# GMSL_DESERIALIZER.net
KiCad netlist of a schematic drawn in Altium Designer
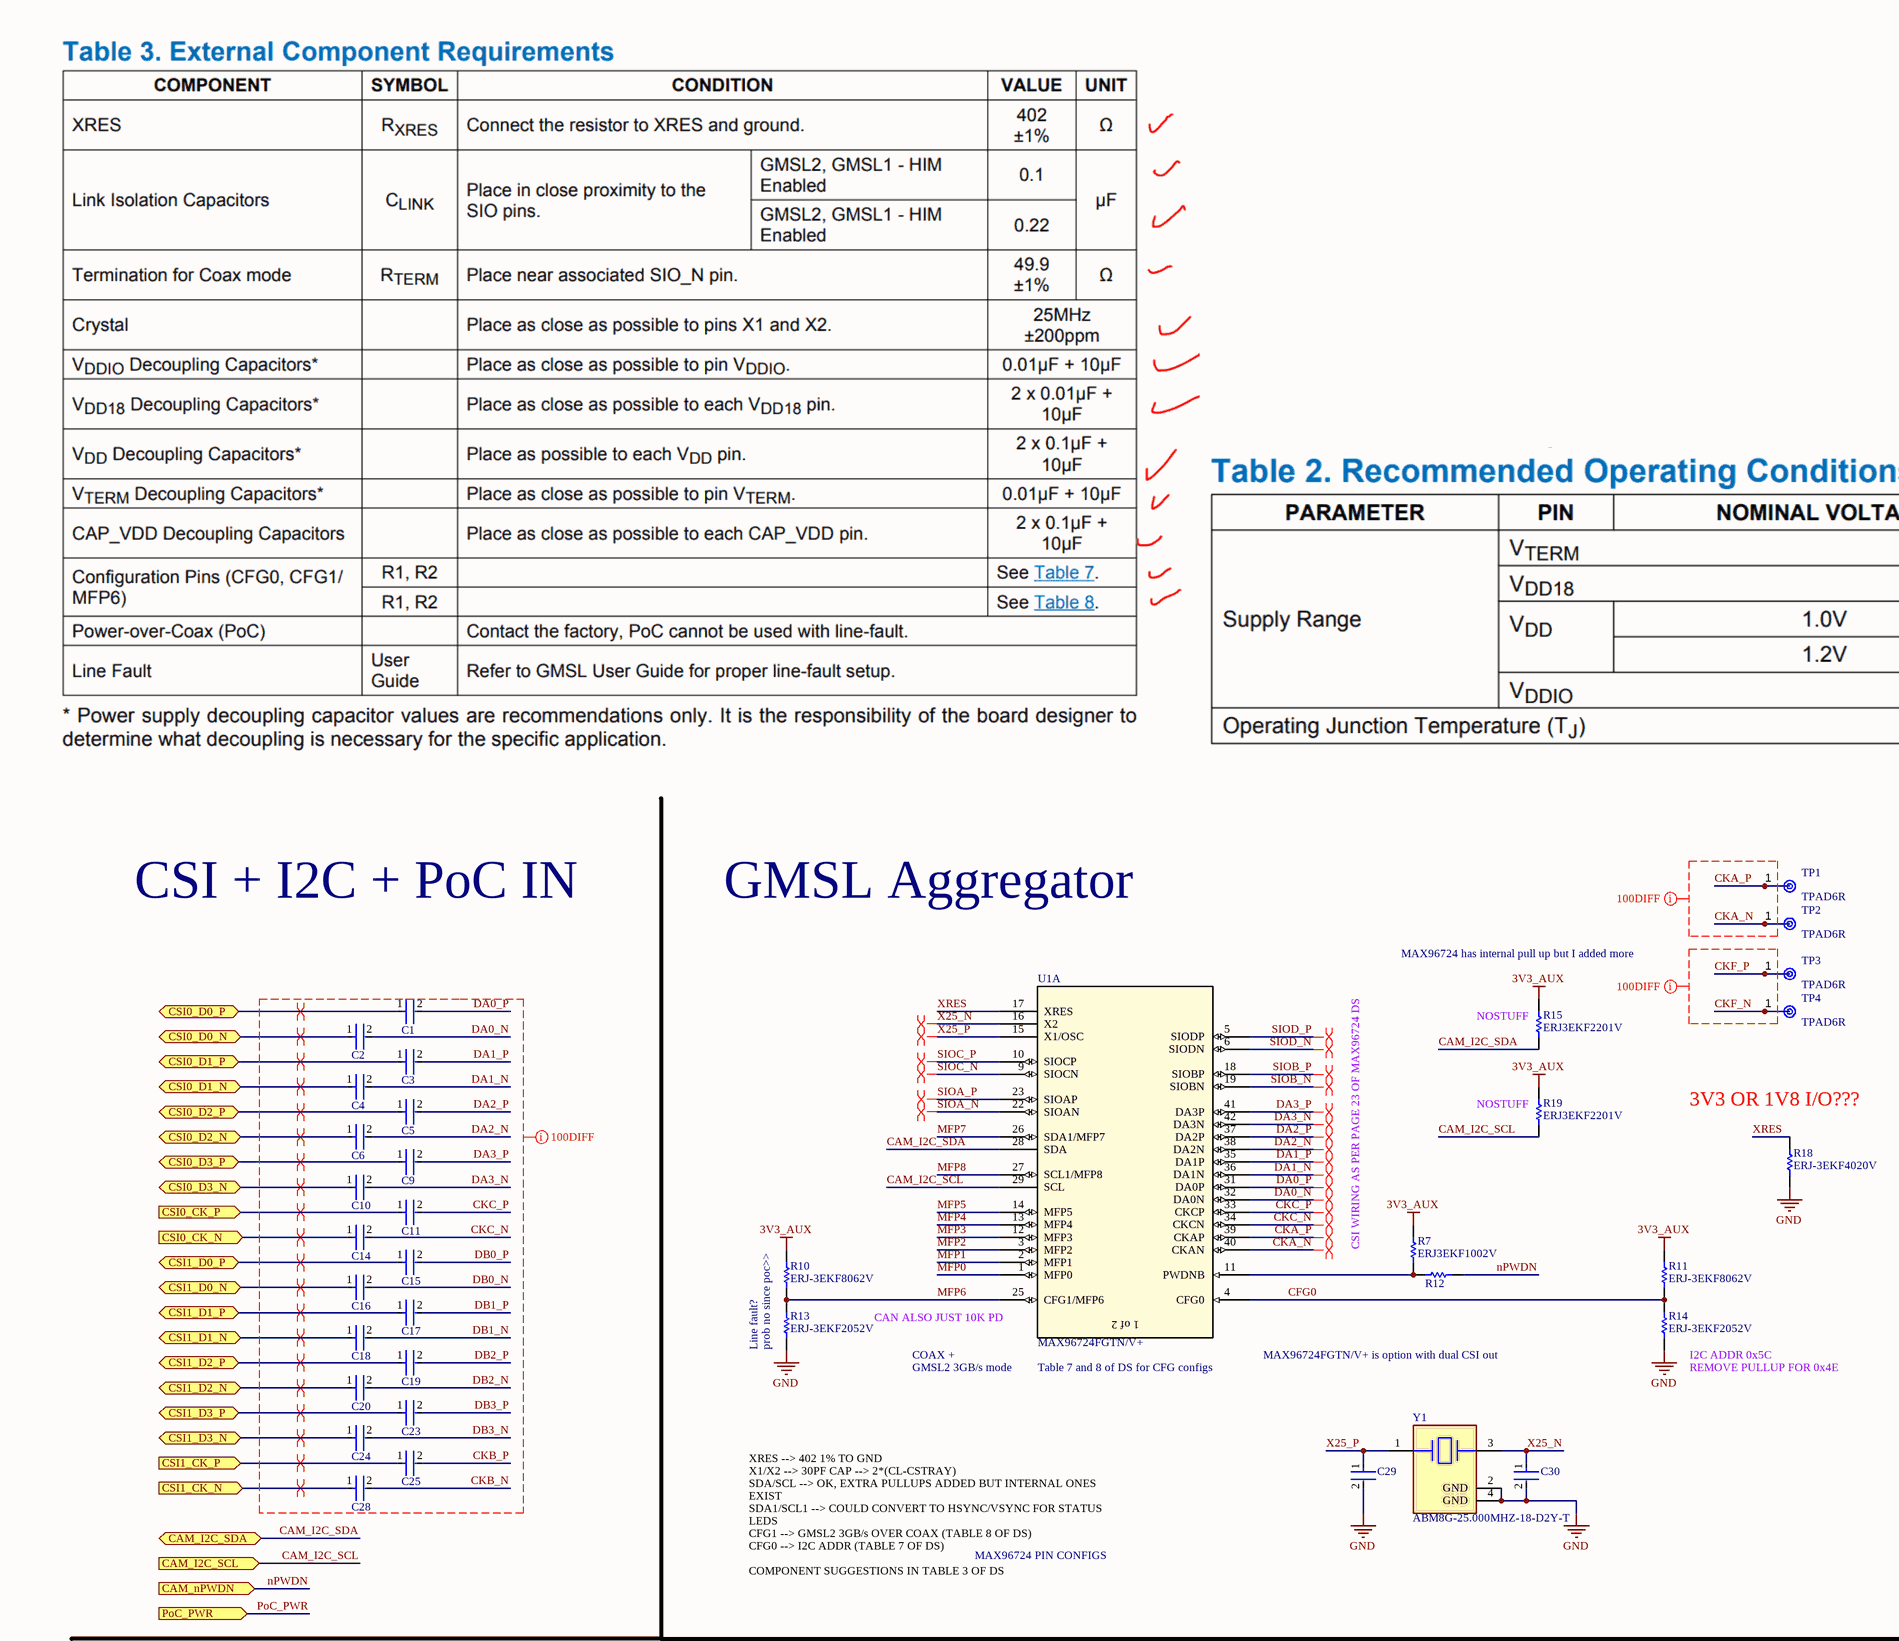
[diagram p0: GMSL_DESERIALIZER.SchDoc, top left]
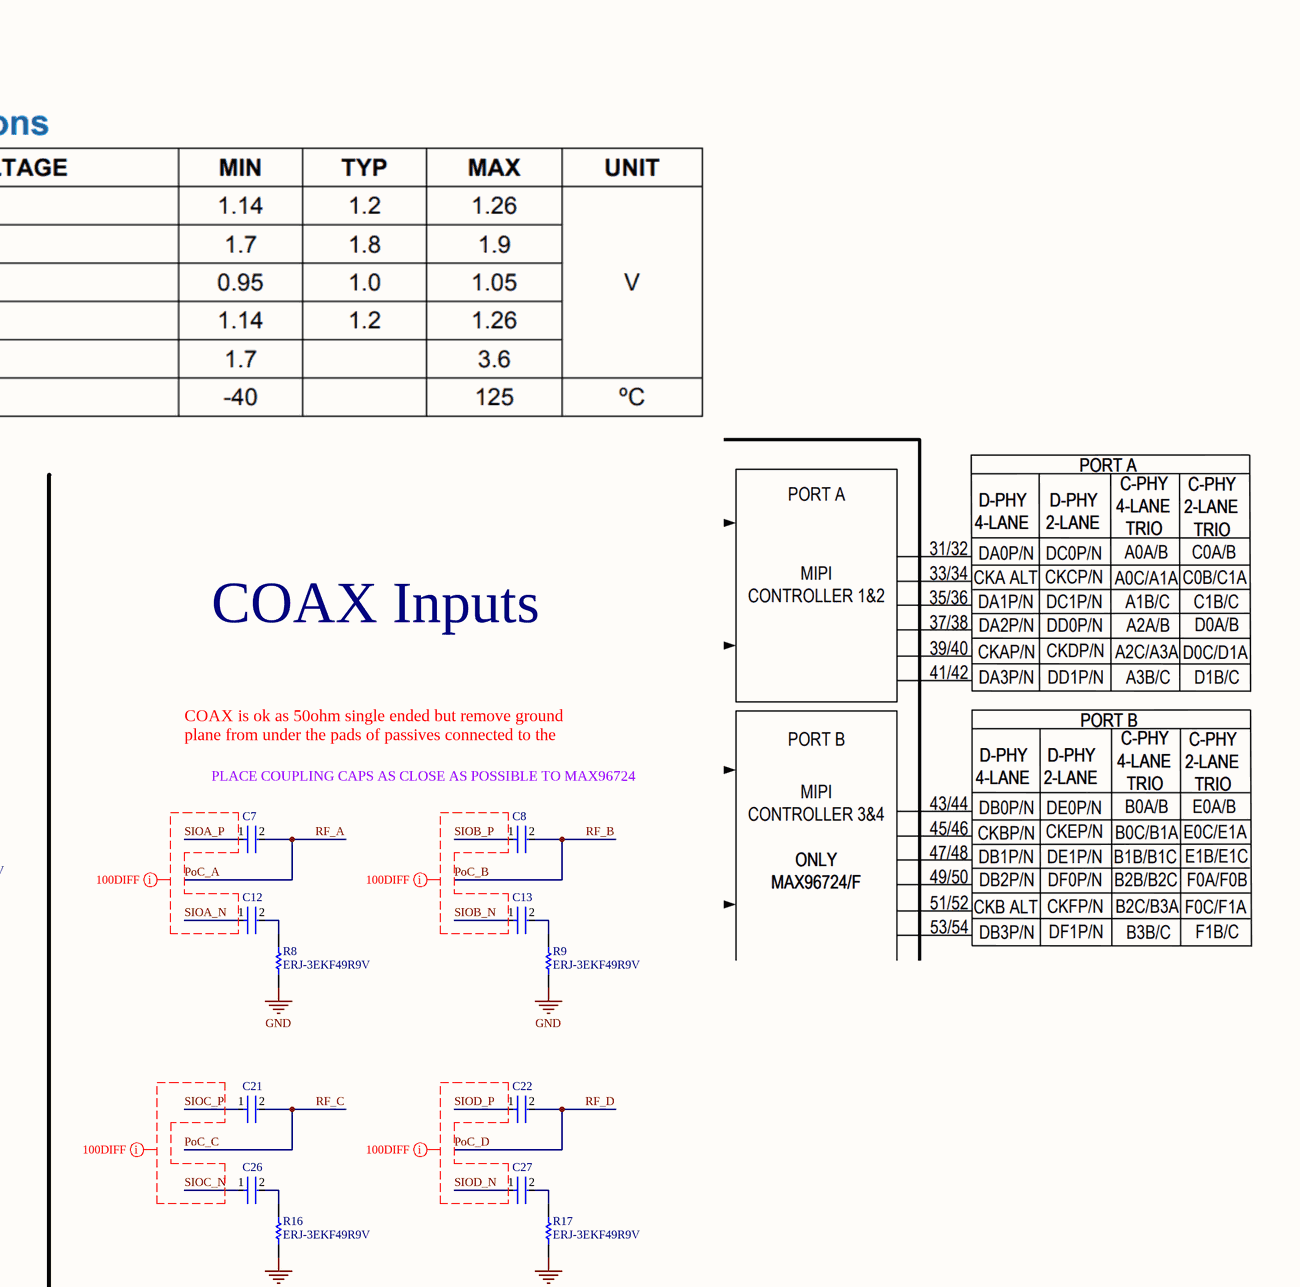
[diagram p1: GMSL_DESERIALIZER.SchDoc, top right]
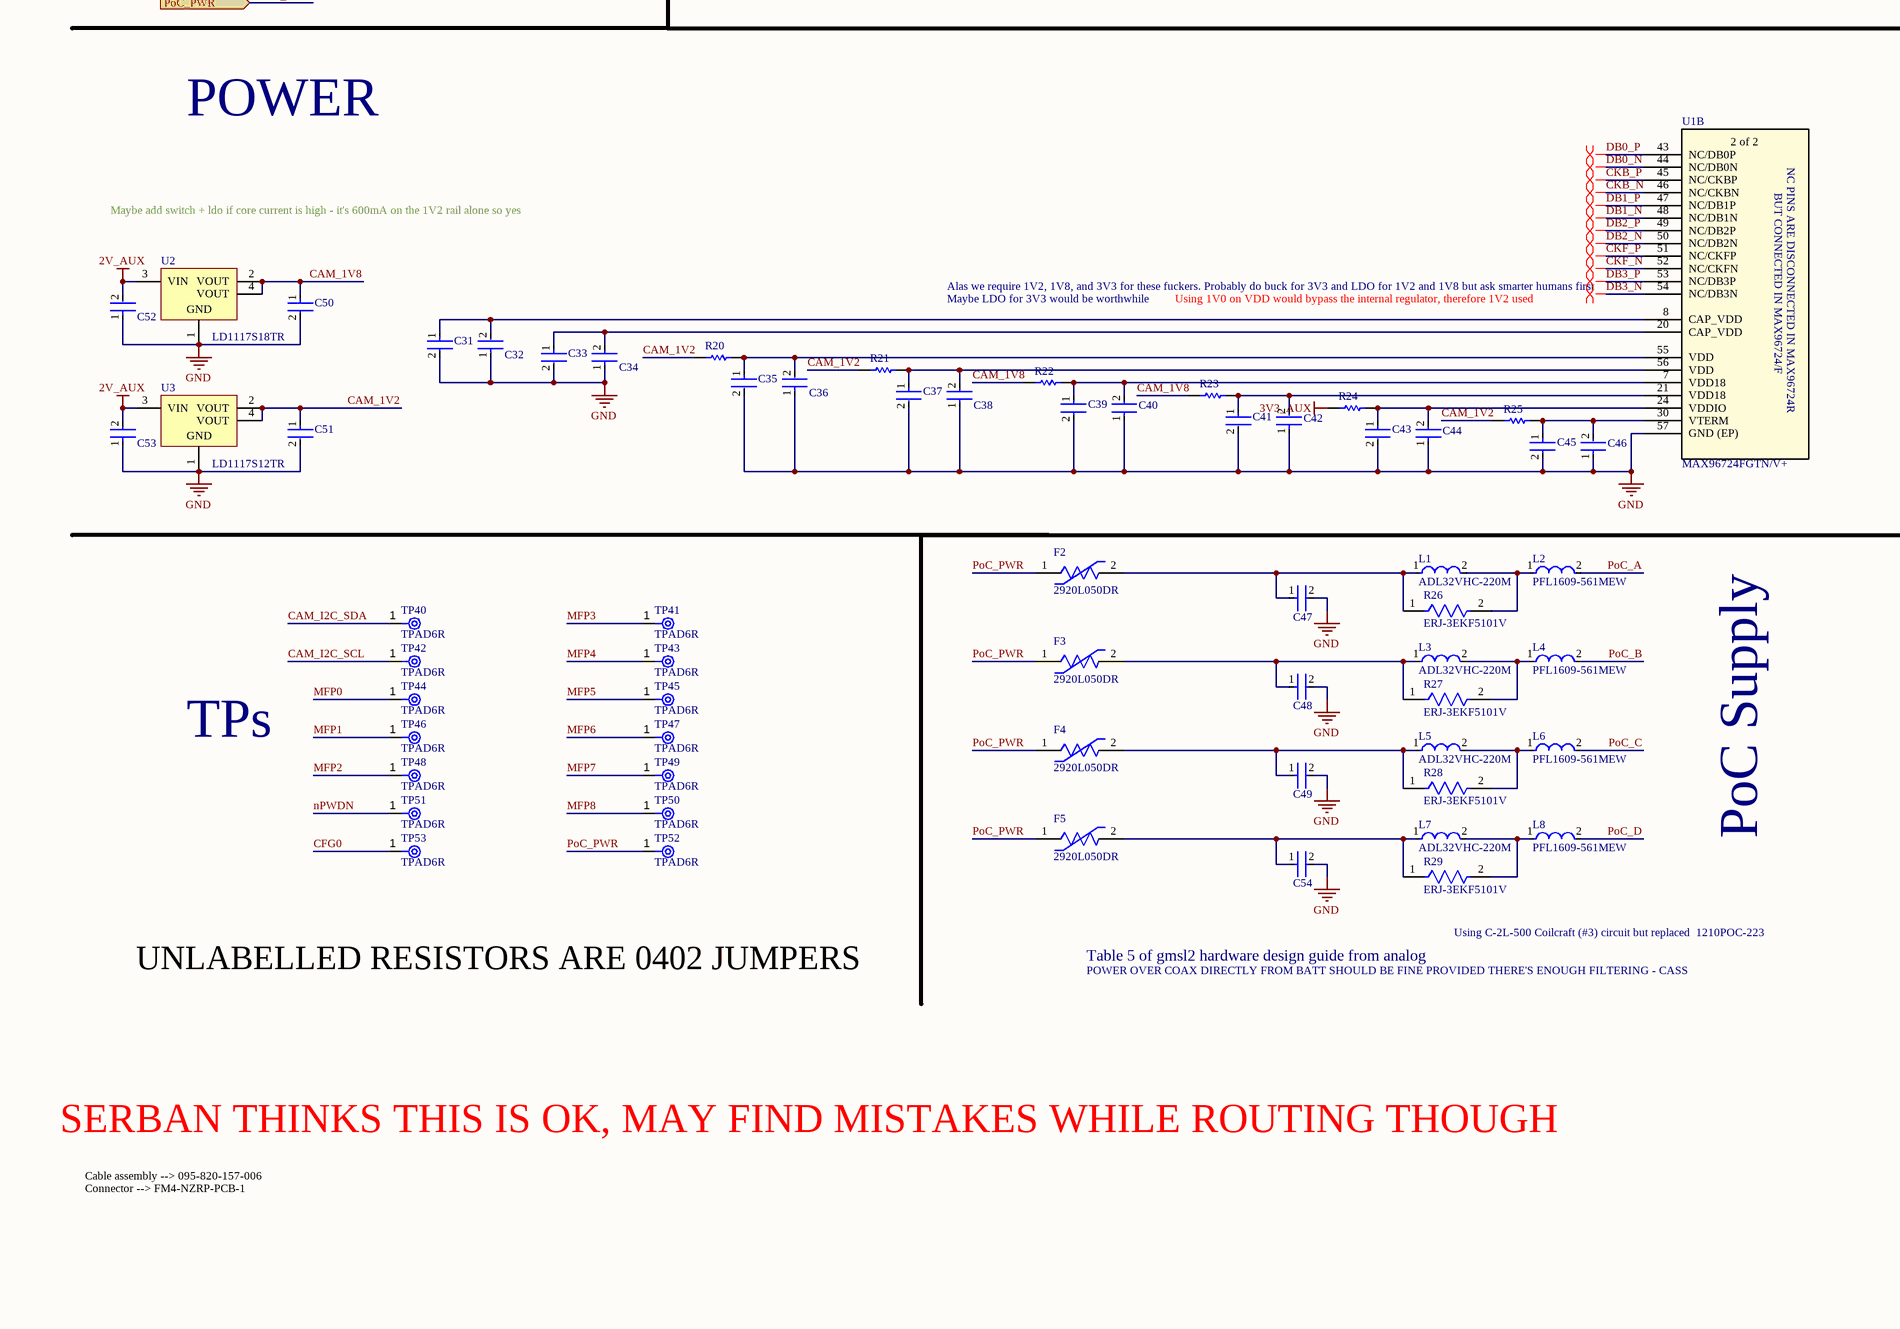
[diagram p2: GMSL_DESERIALIZER.SchDoc, bottom left]
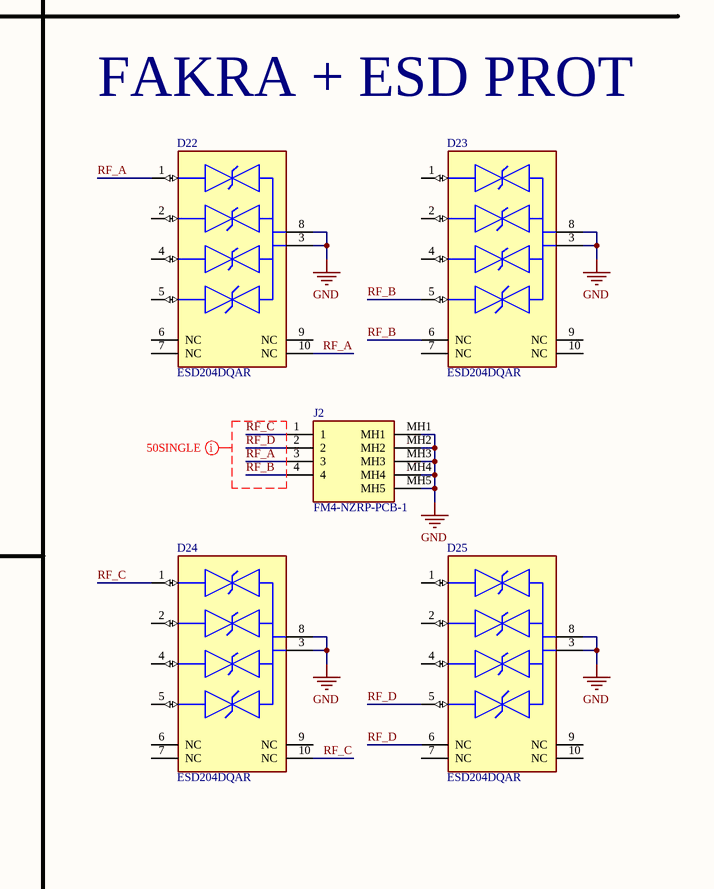
[diagram p3: GMSL_DESERIALIZER.SchDoc, bottom right]

(export (version "E")
  (design (tool "Eeschema 10.0.6"))
  (components
    (comp (ref "C1")
      (value "C1005X7R1H104K050BB")
      (footprint "FP-C1005-050-0_05-IPC_C")
      (description "Multilayer Ceramic Capacitors 100nF ±10% 50V X7R SMD 0402")
      (fields (field (name "VOLTAGE") "50V") (field (name "TOLERANCE") "10%"))
      (libsource (lib "Altium Content Vault") (part "b4654b650e69147ec39a6b967a45e02"))
    )
    (comp (ref "C2")
      (value "C1005X7R1H104K050BB")
      (footprint "FP-C1005-050-0_05-IPC_C")
      (description "Multilayer Ceramic Capacitors 100nF ±10% 50V X7R SMD 0402")
      (fields (field (name "VOLTAGE") "50V") (field (name "TOLERANCE") "10%"))
      (libsource (lib "Altium Content Vault") (part "b4654b650e69147ec39a6b967a45e02"))
    )
    (comp (ref "C3")
      (value "C1005X7R1H104K050BB")
      (footprint "FP-C1005-050-0_05-IPC_C")
      (description "Multilayer Ceramic Capacitors 100nF ±10% 50V X7R SMD 0402")
      (fields (field (name "VOLTAGE") "50V") (field (name "TOLERANCE") "10%"))
      (libsource (lib "Altium Content Vault") (part "b4654b650e69147ec39a6b967a45e02"))
    )
    (comp (ref "C4")
      (value "C1005X7R1H104K050BB")
      (footprint "FP-C1005-050-0_05-IPC_C")
      (description "Multilayer Ceramic Capacitors 100nF ±10% 50V X7R SMD 0402")
      (fields (field (name "VOLTAGE") "50V") (field (name "TOLERANCE") "10%"))
      (libsource (lib "Altium Content Vault") (part "b4654b650e69147ec39a6b967a45e02"))
    )
    (comp (ref "C5")
      (value "C1005X7R1H104K050BB")
      (footprint "FP-C1005-050-0_05-IPC_C")
      (description "Multilayer Ceramic Capacitors 100nF ±10% 50V X7R SMD 0402")
      (fields (field (name "VOLTAGE") "50V") (field (name "TOLERANCE") "10%"))
      (libsource (lib "Altium Content Vault") (part "b4654b650e69147ec39a6b967a45e02"))
    )
    (comp (ref "C6")
      (value "C1005X7R1H104K050BB")
      (footprint "FP-C1005-050-0_05-IPC_C")
      (description "Multilayer Ceramic Capacitors 100nF ±10% 50V X7R SMD 0402")
      (fields (field (name "VOLTAGE") "50V") (field (name "TOLERANCE") "10%"))
      (libsource (lib "Altium Content Vault") (part "b4654b650e69147ec39a6b967a45e02"))
    )
    (comp (ref "C7")
      (value "C1005X7R1A224K050BB")
      (footprint "FP-C1005-050-0_05-IPC_C")
      (description "Multilayer Ceramic Capacitors 220nF ±10% 10V X7R SMD 0402")
      (fields (field (name "TOLERANCE") "10%"))
      (libsource (lib "Altium Content Vault") (part "b4654b650e69147ec39a6b967a45e02"))
    )
    (comp (ref "C8")
      (value "C1005X7R1A224K050BB")
      (footprint "FP-C1005-050-0_05-IPC_C")
      (description "Multilayer Ceramic Capacitors 220nF ±10% 10V X7R SMD 0402")
      (fields (field (name "TOLERANCE") "10%"))
      (libsource (lib "Altium Content Vault") (part "b4654b650e69147ec39a6b967a45e02"))
    )
    (comp (ref "C9")
      (value "C1005X7R1H104K050BB")
      (footprint "FP-C1005-050-0_05-IPC_C")
      (description "Multilayer Ceramic Capacitors 100nF ±10% 50V X7R SMD 0402")
      (fields (field (name "VOLTAGE") "50V") (field (name "TOLERANCE") "10%"))
      (libsource (lib "Altium Content Vault") (part "b4654b650e69147ec39a6b967a45e02"))
    )
    (comp (ref "C10")
      (value "C1005X7R1H104K050BB")
      (footprint "FP-C1005-050-0_05-IPC_C")
      (description "Multilayer Ceramic Capacitors 100nF ±10% 50V X7R SMD 0402")
      (fields (field (name "VOLTAGE") "50V") (field (name "TOLERANCE") "10%"))
      (libsource (lib "Altium Content Vault") (part "b4654b650e69147ec39a6b967a45e02"))
    )
    (comp (ref "C11")
      (value "C1005X7R1H104K050BB")
      (footprint "FP-C1005-050-0_05-IPC_C")
      (description "Multilayer Ceramic Capacitors 100nF ±10% 50V X7R SMD 0402")
      (fields (field (name "VOLTAGE") "50V") (field (name "TOLERANCE") "10%"))
      (libsource (lib "Altium Content Vault") (part "b4654b650e69147ec39a6b967a45e02"))
    )
    (comp (ref "C12")
      (value "C1005X7R1A224K050BB")
      (footprint "FP-C1005-050-0_05-IPC_C")
      (description "Multilayer Ceramic Capacitors 220nF ±10% 10V X7R SMD 0402")
      (fields (field (name "TOLERANCE") "10%"))
      (libsource (lib "Altium Content Vault") (part "b4654b650e69147ec39a6b967a45e02"))
    )
    (comp (ref "C13")
      (value "C1005X7R1A224K050BB")
      (footprint "FP-C1005-050-0_05-IPC_C")
      (description "Multilayer Ceramic Capacitors 220nF ±10% 10V X7R SMD 0402")
      (fields (field (name "TOLERANCE") "10%"))
      (libsource (lib "Altium Content Vault") (part "b4654b650e69147ec39a6b967a45e02"))
    )
    (comp (ref "C14")
      (value "C1005X7R1H104K050BB")
      (footprint "FP-C1005-050-0_05-IPC_C")
      (description "Multilayer Ceramic Capacitors 100nF ±10% 50V X7R SMD 0402")
      (fields (field (name "VOLTAGE") "50V") (field (name "TOLERANCE") "10%"))
      (libsource (lib "Altium Content Vault") (part "b4654b650e69147ec39a6b967a45e02"))
    )
    (comp (ref "C15")
      (value "C1005X7R1H104K050BB")
      (footprint "FP-C1005-050-0_05-IPC_C")
      (description "Multilayer Ceramic Capacitors 100nF ±10% 50V X7R SMD 0402")
      (fields (field (name "VOLTAGE") "50V") (field (name "TOLERANCE") "10%"))
      (libsource (lib "Altium Content Vault") (part "b4654b650e69147ec39a6b967a45e02"))
    )
    (comp (ref "C16")
      (value "C1005X7R1H104K050BB")
      (footprint "FP-C1005-050-0_05-IPC_C")
      (description "Multilayer Ceramic Capacitors 100nF ±10% 50V X7R SMD 0402")
      (fields (field (name "VOLTAGE") "50V") (field (name "TOLERANCE") "10%"))
      (libsource (lib "Altium Content Vault") (part "b4654b650e69147ec39a6b967a45e02"))
    )
    (comp (ref "C17")
      (value "C1005X7R1H104K050BB")
      (footprint "FP-C1005-050-0_05-IPC_C")
      (description "Multilayer Ceramic Capacitors 100nF ±10% 50V X7R SMD 0402")
      (fields (field (name "VOLTAGE") "50V") (field (name "TOLERANCE") "10%"))
      (libsource (lib "Altium Content Vault") (part "b4654b650e69147ec39a6b967a45e02"))
    )
    (comp (ref "C18")
      (value "C1005X7R1H104K050BB")
      (footprint "FP-C1005-050-0_05-IPC_C")
      (description "Multilayer Ceramic Capacitors 100nF ±10% 50V X7R SMD 0402")
      (fields (field (name "VOLTAGE") "50V") (field (name "TOLERANCE") "10%"))
      (libsource (lib "Altium Content Vault") (part "b4654b650e69147ec39a6b967a45e02"))
    )
    (comp (ref "C19")
      (value "C1005X7R1H104K050BB")
      (footprint "FP-C1005-050-0_05-IPC_C")
      (description "Multilayer Ceramic Capacitors 100nF ±10% 50V X7R SMD 0402")
      (fields (field (name "VOLTAGE") "50V") (field (name "TOLERANCE") "10%"))
      (libsource (lib "Altium Content Vault") (part "b4654b650e69147ec39a6b967a45e02"))
    )
    (comp (ref "C20")
      (value "C1005X7R1H104K050BB")
      (footprint "FP-C1005-050-0_05-IPC_C")
      (description "Multilayer Ceramic Capacitors 100nF ±10% 50V X7R SMD 0402")
      (fields (field (name "VOLTAGE") "50V") (field (name "TOLERANCE") "10%"))
      (libsource (lib "Altium Content Vault") (part "b4654b650e69147ec39a6b967a45e02"))
    )
    (comp (ref "C21")
      (value "C1005X7R1A224K050BB")
      (footprint "FP-C1005-050-0_05-IPC_C")
      (description "Multilayer Ceramic Capacitors 220nF ±10% 10V X7R SMD 0402")
      (fields (field (name "TOLERANCE") "10%"))
      (libsource (lib "Altium Content Vault") (part "b4654b650e69147ec39a6b967a45e02"))
    )
    (comp (ref "C22")
      (value "C1005X7R1A224K050BB")
      (footprint "FP-C1005-050-0_05-IPC_C")
      (description "Multilayer Ceramic Capacitors 220nF ±10% 10V X7R SMD 0402")
      (fields (field (name "TOLERANCE") "10%"))
      (libsource (lib "Altium Content Vault") (part "b4654b650e69147ec39a6b967a45e02"))
    )
    (comp (ref "C23")
      (value "C1005X7R1H104K050BB")
      (footprint "FP-C1005-050-0_05-IPC_C")
      (description "Multilayer Ceramic Capacitors 100nF ±10% 50V X7R SMD 0402")
      (fields (field (name "VOLTAGE") "50V") (field (name "TOLERANCE") "10%"))
      (libsource (lib "Altium Content Vault") (part "b4654b650e69147ec39a6b967a45e02"))
    )
    (comp (ref "C24")
      (value "C1005X7R1H104K050BB")
      (footprint "FP-C1005-050-0_05-IPC_C")
      (description "Multilayer Ceramic Capacitors 100nF ±10% 50V X7R SMD 0402")
      (fields (field (name "VOLTAGE") "50V") (field (name "TOLERANCE") "10%"))
      (libsource (lib "Altium Content Vault") (part "b4654b650e69147ec39a6b967a45e02"))
    )
    (comp (ref "C25")
      (value "C1005X7R1H104K050BB")
      (footprint "FP-C1005-050-0_05-IPC_C")
      (description "Multilayer Ceramic Capacitors 100nF ±10% 50V X7R SMD 0402")
      (fields (field (name "VOLTAGE") "50V") (field (name "TOLERANCE") "10%"))
      (libsource (lib "Altium Content Vault") (part "b4654b650e69147ec39a6b967a45e02"))
    )
    (comp (ref "C26")
      (value "C1005X7R1A224K050BB")
      (footprint "FP-C1005-050-0_05-IPC_C")
      (description "Multilayer Ceramic Capacitors 220nF ±10% 10V X7R SMD 0402")
      (fields (field (name "TOLERANCE") "10%"))
      (libsource (lib "Altium Content Vault") (part "b4654b650e69147ec39a6b967a45e02"))
    )
    (comp (ref "C27")
      (value "C1005X7R1A224K050BB")
      (footprint "FP-C1005-050-0_05-IPC_C")
      (description "Multilayer Ceramic Capacitors 220nF ±10% 10V X7R SMD 0402")
      (fields (field (name "TOLERANCE") "10%"))
      (libsource (lib "Altium Content Vault") (part "b4654b650e69147ec39a6b967a45e02"))
    )
    (comp (ref "C28")
      (value "C1005X7R1H104K050BB")
      (footprint "FP-C1005-050-0_05-IPC_C")
      (description "Multilayer Ceramic Capacitors 100nF ±10% 50V X7R SMD 0402")
      (fields (field (name "VOLTAGE") "50V") (field (name "TOLERANCE") "10%"))
      (libsource (lib "Altium Content Vault") (part "b4654b650e69147ec39a6b967a45e02"))
    )
    (comp (ref "C29")
      (value "C0603C300J5GACTU")
      (footprint "FP-C0603C-CF-MFG")
      (description "CAP CER 30PF 50V 5% NP0 0603")
      (fields
        (field (name "MANUFACTURER") "KEMET")
        (field (name "OCTOPART") "https://octopart.com/c0603c300j5gactu-kemet-199455")
      )
      (libsource (lib "Altium Content Vault") (part "b4654b650e69147ec39a6b967a45e02"))
    )
    (comp (ref "C30")
      (value "C0603C300J5GACTU")
      (footprint "FP-C0603C-CF-MFG")
      (description "CAP CER 30PF 50V 5% NP0 0603")
      (fields
        (field (name "MANUFACTURER") "KEMET")
        (field (name "OCTOPART") "https://octopart.com/c0603c300j5gactu-kemet-199455")
      )
      (libsource (lib "Altium Content Vault") (part "b4654b650e69147ec39a6b967a45e02"))
    )
    (comp (ref "C31")
      (value "CL05A106MP5NUNC")
      (footprint "FP-CL05A106MP5NUNC-MFG")
      (description "CAP CER 10UF 10V X5R 0402")
      (fields
        (field (name "OCTOPART") "https://octopart.com/cl05a106mp5nunc-samsung-22457395")
        (field (name "TOLERANCE") "20%")
      )
      (libsource (lib "Altium Content Vault") (part "b4654b650e69147ec39a6b967a45e02"))
    )
    (comp (ref "C32")
      (value "C1005X7R1H104K050BB")
      (footprint "FP-C1005-050-0_05-IPC_C")
      (description "Multilayer Ceramic Capacitors 100nF ±10% 50V X7R SMD 0402")
      (fields (field (name "VOLTAGE") "50V") (field (name "TOLERANCE") "10%"))
      (libsource (lib "Altium Content Vault") (part "b4654b650e69147ec39a6b967a45e02"))
    )
    (comp (ref "C33")
      (value "CL05A106MP5NUNC")
      (footprint "FP-CL05A106MP5NUNC-MFG")
      (description "CAP CER 10UF 10V X5R 0402")
      (fields
        (field (name "OCTOPART") "https://octopart.com/cl05a106mp5nunc-samsung-22457395")
        (field (name "TOLERANCE") "20%")
      )
      (libsource (lib "Altium Content Vault") (part "b4654b650e69147ec39a6b967a45e02"))
    )
    (comp (ref "C34")
      (value "C1005X7R1H104K050BB")
      (footprint "FP-C1005-050-0_05-IPC_C")
      (description "Multilayer Ceramic Capacitors 100nF ±10% 50V X7R SMD 0402")
      (fields (field (name "VOLTAGE") "50V") (field (name "TOLERANCE") "10%"))
      (libsource (lib "Altium Content Vault") (part "b4654b650e69147ec39a6b967a45e02"))
    )
    (comp (ref "C35")
      (value "CL05A106MP5NUNC")
      (footprint "FP-CL05A106MP5NUNC-MFG")
      (description "CAP CER 10UF 10V X5R 0402")
      (fields
        (field (name "OCTOPART") "https://octopart.com/cl05a106mp5nunc-samsung-22457395")
        (field (name "TOLERANCE") "20%")
      )
      (libsource (lib "Altium Content Vault") (part "b4654b650e69147ec39a6b967a45e02"))
    )
    (comp (ref "C36")
      (value "C1005X7R1H104K050BB")
      (footprint "FP-C1005-050-0_05-IPC_C")
      (description "Multilayer Ceramic Capacitors 100nF ±10% 50V X7R SMD 0402")
      (fields (field (name "VOLTAGE") "50V") (field (name "TOLERANCE") "10%"))
      (libsource (lib "Altium Content Vault") (part "b4654b650e69147ec39a6b967a45e02"))
    )
    (comp (ref "C37")
      (value "CL05A106MP5NUNC")
      (footprint "FP-CL05A106MP5NUNC-MFG")
      (description "CAP CER 10UF 10V X5R 0402")
      (fields
        (field (name "OCTOPART") "https://octopart.com/cl05a106mp5nunc-samsung-22457395")
        (field (name "TOLERANCE") "20%")
      )
      (libsource (lib "Altium Content Vault") (part "b4654b650e69147ec39a6b967a45e02"))
    )
    (comp (ref "C38")
      (value "C1005X7R1H104K050BB")
      (footprint "FP-C1005-050-0_05-IPC_C")
      (description "Multilayer Ceramic Capacitors 100nF ±10% 50V X7R SMD 0402")
      (fields (field (name "VOLTAGE") "50V") (field (name "TOLERANCE") "10%"))
      (libsource (lib "Altium Content Vault") (part "b4654b650e69147ec39a6b967a45e02"))
    )
    (comp (ref "C39")
      (value "CL05A106MP5NUNC")
      (footprint "FP-CL05A106MP5NUNC-MFG")
      (description "CAP CER 10UF 10V X5R 0402")
      (fields
        (field (name "OCTOPART") "https://octopart.com/cl05a106mp5nunc-samsung-22457395")
        (field (name "TOLERANCE") "20%")
      )
      (libsource (lib "Altium Content Vault") (part "b4654b650e69147ec39a6b967a45e02"))
    )
    (comp (ref "C40")
      (value "C0402C103M5RACTU")
      (footprint "FP-C0402-BB-MFG")
      (description "CAP CER 10000PF 50V 20% X7R 0402")
      (fields
        (field (name "TOLERANCE") "0.2")
        (field (name "OCTOPART") "https://octopart.com/c0402c103m5ractu-kemet-17125571")
      )
      (libsource (lib "Altium Content Vault") (part "b4654b650e69147ec39a6b967a45e02"))
    )
    (comp (ref "C41")
      (value "CL05A106MP5NUNC")
      (footprint "FP-CL05A106MP5NUNC-MFG")
      (description "CAP CER 10UF 10V X5R 0402")
      (fields
        (field (name "OCTOPART") "https://octopart.com/cl05a106mp5nunc-samsung-22457395")
        (field (name "TOLERANCE") "20%")
      )
      (libsource (lib "Altium Content Vault") (part "b4654b650e69147ec39a6b967a45e02"))
    )
    (comp (ref "C42")
      (value "C0402C103M5RACTU")
      (footprint "FP-C0402-BB-MFG")
      (description "CAP CER 10000PF 50V 20% X7R 0402")
      (fields
        (field (name "TOLERANCE") "0.2")
        (field (name "OCTOPART") "https://octopart.com/c0402c103m5ractu-kemet-17125571")
      )
      (libsource (lib "Altium Content Vault") (part "b4654b650e69147ec39a6b967a45e02"))
    )
    (comp (ref "C43")
      (value "CL05A106MP5NUNC")
      (footprint "FP-CL05A106MP5NUNC-MFG")
      (description "CAP CER 10UF 10V X5R 0402")
      (fields
        (field (name "OCTOPART") "https://octopart.com/cl05a106mp5nunc-samsung-22457395")
        (field (name "TOLERANCE") "20%")
      )
      (libsource (lib "Altium Content Vault") (part "b4654b650e69147ec39a6b967a45e02"))
    )
    (comp (ref "C44")
      (value "C0402C103M5RACTU")
      (footprint "FP-C0402-BB-MFG")
      (description "CAP CER 10000PF 50V 20% X7R 0402")
      (fields
        (field (name "TOLERANCE") "0.2")
        (field (name "OCTOPART") "https://octopart.com/c0402c103m5ractu-kemet-17125571")
      )
      (libsource (lib "Altium Content Vault") (part "b4654b650e69147ec39a6b967a45e02"))
    )
    (comp (ref "C45")
      (value "CL05A106MP5NUNC")
      (footprint "FP-CL05A106MP5NUNC-MFG")
      (description "CAP CER 10UF 10V X5R 0402")
      (fields
        (field (name "OCTOPART") "https://octopart.com/cl05a106mp5nunc-samsung-22457395")
        (field (name "TOLERANCE") "20%")
      )
      (libsource (lib "Altium Content Vault") (part "b4654b650e69147ec39a6b967a45e02"))
    )
    (comp (ref "C46")
      (value "C0402C103M5RACTU")
      (footprint "FP-C0402-BB-MFG")
      (description "CAP CER 10000PF 50V 20% X7R 0402")
      (fields
        (field (name "TOLERANCE") "0.2")
        (field (name "OCTOPART") "https://octopart.com/c0402c103m5ractu-kemet-17125571")
      )
      (libsource (lib "Altium Content Vault") (part "b4654b650e69147ec39a6b967a45e02"))
    )
    (comp (ref "C47")
      (value "GRM21BR61E226ME44L")
      (footprint "FP-GRM21B-0_2-e0_2_0_7-IPC_B")
      (description "Chip Multilayer Ceramic Capacitors for General Purpose, 0805, 22uF, X5R, 15%, 20%, 25V")
      (fields (field (name "TOLERANCE") "20%") (field (name "VOLTAGE") "25V"))
      (libsource (lib "Altium Content Vault") (part "b4654b650e69147ec39a6b967a45e02"))
    )
    (comp (ref "C48")
      (value "GRM21BR61E226ME44L")
      (footprint "FP-GRM21B-0_2-e0_2_0_7-IPC_B")
      (description "Chip Multilayer Ceramic Capacitors for General Purpose, 0805, 22uF, X5R, 15%, 20%, 25V")
      (fields (field (name "TOLERANCE") "20%") (field (name "VOLTAGE") "25V"))
      (libsource (lib "Altium Content Vault") (part "b4654b650e69147ec39a6b967a45e02"))
    )
    (comp (ref "C49")
      (value "GRM21BR61E226ME44L")
      (footprint "FP-GRM21B-0_2-e0_2_0_7-IPC_B")
      (description "Chip Multilayer Ceramic Capacitors for General Purpose, 0805, 22uF, X5R, 15%, 20%, 25V")
      (fields (field (name "TOLERANCE") "20%") (field (name "VOLTAGE") "25V"))
      (libsource (lib "Altium Content Vault") (part "b4654b650e69147ec39a6b967a45e02"))
    )
    (comp (ref "C50")
      (value "GRM188R60J106ME47D")
      (footprint "FP-GRM188-0_1-e0_2_0_55-IPC_A")
      (description "Chip Multilayer Ceramic Capacitors for General Purpose, 0603, 10uF, X5R, 15%, 20%, 6.3V")
      (fields (field (name "VOLTAGE") "6.3V") (field (name "TOLERANCE") "20%"))
      (libsource (lib "Altium Content Vault") (part "02cd4be3c70576c341d710602a673aa"))
    )
    (comp (ref "C51")
      (value "GRM188R60J106ME47D")
      (footprint "FP-GRM188-0_1-e0_2_0_55-IPC_A")
      (description "Chip Multilayer Ceramic Capacitors for General Purpose, 0603, 10uF, X5R, 15%, 20%, 6.3V")
      (fields (field (name "VOLTAGE") "6.3V") (field (name "TOLERANCE") "20%"))
      (libsource (lib "Altium Content Vault") (part "02cd4be3c70576c341d710602a673aa"))
    )
    (comp (ref "C52")
      (value "C1005X7R1H104K050BB")
      (footprint "FP-C1005-050-0_05-IPC_C")
      (description "Multilayer Ceramic Capacitors 100nF ±10% 50V X7R SMD 0402")
      (fields (field (name "VOLTAGE") "50V") (field (name "TOLERANCE") "10%"))
      (libsource (lib "Altium Content Vault") (part "b4654b650e69147ec39a6b967a45e02"))
    )
    (comp (ref "C53")
      (value "C1005X7R1H104K050BB")
      (footprint "FP-C1005-050-0_05-IPC_C")
      (description "Multilayer Ceramic Capacitors 100nF ±10% 50V X7R SMD 0402")
      (fields (field (name "VOLTAGE") "50V") (field (name "TOLERANCE") "10%"))
      (libsource (lib "Altium Content Vault") (part "b4654b650e69147ec39a6b967a45e02"))
    )
    (comp (ref "C54")
      (value "GRM21BR61E226ME44L")
      (footprint "FP-GRM21B-0_2-e0_2_0_7-IPC_B")
      (description "Chip Multilayer Ceramic Capacitors for General Purpose, 0805, 22uF, X5R, 15%, 20%, 25V")
      (fields (field (name "TOLERANCE") "20%") (field (name "VOLTAGE") "25V"))
      (libsource (lib "Altium Content Vault") (part "b4654b650e69147ec39a6b967a45e02"))
    )
    (comp (ref "D22")
      (value "ESD204DQAR")
      (footprint "FP-DQA0010A-MFG")
      (description "4-CHANNEL LOW-CAPACITANCE SURGE")
      (fields
        (field (name "MANUFACTURER") "Texas Instruments")
        (field (name "OCTOPART") "https://octopart.com/esd204dqar-texas+instruments-89917476")
      )
      (libsource (lib "Altium Content Vault") (part "1465e58c1818c7767b55926832f0bf5"))
    )
    (comp (ref "D23")
      (value "ESD204DQAR")
      (footprint "FP-DQA0010A-MFG")
      (description "4-CHANNEL LOW-CAPACITANCE SURGE")
      (fields
        (field (name "MANUFACTURER") "Texas Instruments")
        (field (name "OCTOPART") "https://octopart.com/esd204dqar-texas+instruments-89917476")
      )
      (libsource (lib "Altium Content Vault") (part "1465e58c1818c7767b55926832f0bf5"))
    )
    (comp (ref "D24")
      (value "ESD204DQAR")
      (footprint "FP-DQA0010A-MFG")
      (description "4-CHANNEL LOW-CAPACITANCE SURGE")
      (fields
        (field (name "MANUFACTURER") "Texas Instruments")
        (field (name "OCTOPART") "https://octopart.com/esd204dqar-texas+instruments-89917476")
      )
      (libsource (lib "Altium Content Vault") (part "1465e58c1818c7767b55926832f0bf5"))
    )
    (comp (ref "D25")
      (value "ESD204DQAR")
      (footprint "FP-DQA0010A-MFG")
      (description "4-CHANNEL LOW-CAPACITANCE SURGE")
      (fields
        (field (name "MANUFACTURER") "Texas Instruments")
        (field (name "OCTOPART") "https://octopart.com/esd204dqar-texas+instruments-89917476")
      )
      (libsource (lib "Altium Content Vault") (part "1465e58c1818c7767b55926832f0bf5"))
    )
    (comp (ref "F2")
      (value "2920L050DR")
      (footprint "FP-2920L050DR-MFG")
      (description "PTC RESET FUSE 60V 500MA 2920")
      (libsource (lib "Altium Content Vault") (part "1c6d77a0208143737455a0c7eb396be"))
    )
    (comp (ref "F3")
      (value "2920L050DR")
      (footprint "FP-2920L050DR-MFG")
      (description "PTC RESET FUSE 60V 500MA 2920")
      (libsource (lib "Altium Content Vault") (part "1c6d77a0208143737455a0c7eb396be"))
    )
    (comp (ref "F4")
      (value "2920L050DR")
      (footprint "FP-2920L050DR-MFG")
      (description "PTC RESET FUSE 60V 500MA 2920")
      (libsource (lib "Altium Content Vault") (part "1c6d77a0208143737455a0c7eb396be"))
    )
    (comp (ref "F5")
      (value "2920L050DR")
      (footprint "FP-2920L050DR-MFG")
      (description "PTC RESET FUSE 60V 500MA 2920")
      (libsource (lib "Altium Content Vault") (part "1c6d77a0208143737455a0c7eb396be"))
    )
    (comp (ref "J2")
      (value "FM4-NZRP-PCB-1")
      (footprint "FM4-NZRP-PCB-1-Footprint-1")
      (description "Connector RF Mini-FAKRA Plug 9GHz 50Ohm Solder Right Angle Through Hole")
      (libsource (lib "Space Concordia") (part "CMP-002-00085-1"))
    )
    (comp (ref "L1")
      (value "ADL32VHC-220M")
      (footprint "FP-1210POC-MFG")
      (description "NOT COILCRAFT - ACTUAL P# --> ADL32VHC-220M\r\n - Power Injection Chokes for PoC")
      (fields
        (field (name "MANUFACTURER") "coilcraft")
        (field (name "OCTOPART") "https://octopart.com/1210poc-223mrc-coilcraft-103207315")
      )
      (libsource (lib "Altium Content Vault") (part "725321dda6339637d4d059423bc1c3c"))
    )
    (comp (ref "L2")
      (value "PFL1609-561MEW")
      (footprint "FP-PFL1609-MFG")
      (description "Fixed Inductors PFL1609 Low Profile 0.56 uH 20 % 1.4 A")
      (fields (field (name "MANUFACTURER") "coilcraft") (field (name "TOLERANCE") "20%"))
      (libsource (lib "Altium Content Vault") (part "725321dda6339637d4d059423bc1c3c"))
    )
    (comp (ref "L3")
      (value "ADL32VHC-220M")
      (footprint "FP-1210POC-MFG")
      (description "NOT COILCRAFT - ACTUAL P# --> ADL32VHC-220M\r\n - Power Injection Chokes for PoC")
      (fields
        (field (name "MANUFACTURER") "coilcraft")
        (field (name "OCTOPART") "https://octopart.com/1210poc-223mrc-coilcraft-103207315")
      )
      (libsource (lib "Altium Content Vault") (part "725321dda6339637d4d059423bc1c3c"))
    )
    (comp (ref "L4")
      (value "PFL1609-561MEW")
      (footprint "FP-PFL1609-MFG")
      (description "Fixed Inductors PFL1609 Low Profile 0.56 uH 20 % 1.4 A")
      (fields (field (name "MANUFACTURER") "coilcraft") (field (name "TOLERANCE") "20%"))
      (libsource (lib "Altium Content Vault") (part "725321dda6339637d4d059423bc1c3c"))
    )
    (comp (ref "L5")
      (value "ADL32VHC-220M")
      (footprint "FP-1210POC-MFG")
      (description "NOT COILCRAFT - ACTUAL P# --> ADL32VHC-220M\r\n - Power Injection Chokes for PoC")
      (fields
        (field (name "MANUFACTURER") "coilcraft")
        (field (name "OCTOPART") "https://octopart.com/1210poc-223mrc-coilcraft-103207315")
      )
      (libsource (lib "Altium Content Vault") (part "725321dda6339637d4d059423bc1c3c"))
    )
    (comp (ref "L6")
      (value "PFL1609-561MEW")
      (footprint "FP-PFL1609-MFG")
      (description "Fixed Inductors PFL1609 Low Profile 0.56 uH 20 % 1.4 A")
      (fields (field (name "MANUFACTURER") "coilcraft") (field (name "TOLERANCE") "20%"))
      (libsource (lib "Altium Content Vault") (part "725321dda6339637d4d059423bc1c3c"))
    )
    (comp (ref "L7")
      (value "ADL32VHC-220M")
      (footprint "FP-1210POC-MFG")
      (description "NOT COILCRAFT - ACTUAL P# --> ADL32VHC-220M\r\n - Power Injection Chokes for PoC")
      (fields
        (field (name "MANUFACTURER") "coilcraft")
        (field (name "OCTOPART") "https://octopart.com/1210poc-223mrc-coilcraft-103207315")
      )
      (libsource (lib "Altium Content Vault") (part "725321dda6339637d4d059423bc1c3c"))
    )
    (comp (ref "L8")
      (value "PFL1609-561MEW")
      (footprint "FP-PFL1609-MFG")
      (description "Fixed Inductors PFL1609 Low Profile 0.56 uH 20 % 1.4 A")
      (fields (field (name "MANUFACTURER") "coilcraft") (field (name "TOLERANCE") "20%"))
      (libsource (lib "Altium Content Vault") (part "725321dda6339637d4d059423bc1c3c"))
    )
    (comp (ref "R7")
      (value "ERJ3EKF1002V")
      (footprint "RESC1609X55X30LL15T15")
      (description "Chip Resistor, 10 KOhm, +/- 1%, 0.1 W, -55 to 155 degC, 0603 (1608 Metric), RoHS, Tape and Reel")
      (fields (field (name "TOLERANCE") "1%") (field (name "MANUFACTURER") "Panasonic"))
      (libsource (lib "Altium Content Vault") (part "RES-2"))
    )
    (comp (ref "R8")
      (value "ERJ-3EKF49R9V")
      (footprint "RESC1608X55X30ML15T15")
      (fields (field (name "MANUFACTURER") "Panasonic"))
      (libsource (lib "Altium Content Vault") (part "RES"))
    )
    (comp (ref "R9")
      (value "ERJ-3EKF49R9V")
      (footprint "RESC1608X55X30ML15T15")
      (fields (field (name "MANUFACTURER") "Panasonic"))
      (libsource (lib "Altium Content Vault") (part "RES"))
    )
    (comp (ref "R10")
      (value "ERJ-3EKF8062V")
      (footprint "RESC1608X55X30LL15T15")
      (fields (field (name "MANUFACTURER") "Panasonic"))
      (libsource (lib "Altium Content Vault") (part "RES"))
    )
    (comp (ref "R11")
      (value "ERJ-3EKF8062V")
      (footprint "RESC1608X55X30LL15T15")
      (fields (field (name "MANUFACTURER") "Panasonic"))
      (libsource (lib "Altium Content Vault") (part "RES"))
    )
    (comp (ref "R12")
      (value "0402 JUMPER")
      (footprint "RESC1005X40X25ML05T05")
      (description "READ THE NAME")
      (libsource (lib "Space Concordia") (part "CMP-009-00206-2"))
    )
    (comp (ref "R13")
      (value "ERJ-3EKF2052V")
      (footprint "RESC1608X55X30NL15T15")
      (fields (field (name "MANUFACTURER") "Panasonic"))
      (libsource (lib "Altium Content Vault") (part "RES"))
    )
    (comp (ref "R14")
      (value "ERJ-3EKF2052V")
      (footprint "RESC1608X55X30NL15T15")
      (fields (field (name "MANUFACTURER") "Panasonic"))
      (libsource (lib "Altium Content Vault") (part "RES"))
    )
    (comp (ref "R15")
      (value "ERJ3EKF2201V")
      (footprint "RESC1608X55X30LL15T15")
      (fields (field (name "MANUFACTURER") "Panasonic"))
      (libsource (lib "Altium Content Vault") (part "RES"))
    )
    (comp (ref "R16")
      (value "ERJ-3EKF49R9V")
      (footprint "RESC1608X55X30ML15T15")
      (fields (field (name "MANUFACTURER") "Panasonic"))
      (libsource (lib "Altium Content Vault") (part "RES"))
    )
    (comp (ref "R17")
      (value "ERJ-3EKF49R9V")
      (footprint "RESC1608X55X30ML15T15")
      (fields (field (name "MANUFACTURER") "Panasonic"))
      (libsource (lib "Altium Content Vault") (part "RES"))
    )
    (comp (ref "R18")
      (value "ERJ-3EKF4020V")
      (footprint "RESC1608X55X30LL15T15")
      (fields (field (name "MANUFACTURER") "Panasonic"))
      (libsource (lib "Altium Content Vault") (part "RES"))
    )
    (comp (ref "R19")
      (value "ERJ3EKF2201V")
      (footprint "RESC1608X55X30LL15T15")
      (fields (field (name "MANUFACTURER") "Panasonic"))
      (libsource (lib "Altium Content Vault") (part "RES"))
    )
    (comp (ref "R20")
      (value "RC0402JR-070RL")
      (footprint "RESC1005X40X25NL05T10")
      (fields (field (name "MANUFACTURER") "Yageo / Phycomp"))
      (libsource (lib "Altium Content Vault") (part "RES"))
    )
    (comp (ref "R21")
      (value "RC0402JR-070RL")
      (footprint "RESC1005X40X25NL05T10")
      (fields (field (name "MANUFACTURER") "Yageo / Phycomp"))
      (libsource (lib "Altium Content Vault") (part "RES"))
    )
    (comp (ref "R22")
      (value "RC0402JR-070RL")
      (footprint "RESC1005X40X25NL05T10")
      (fields (field (name "MANUFACTURER") "Yageo / Phycomp"))
      (libsource (lib "Altium Content Vault") (part "RES"))
    )
    (comp (ref "R23")
      (value "RC0402JR-070RL")
      (footprint "RESC1005X40X25NL05T10")
      (fields (field (name "MANUFACTURER") "Yageo / Phycomp"))
      (libsource (lib "Altium Content Vault") (part "RES"))
    )
    (comp (ref "R24")
      (value "RC0402JR-070RL")
      (footprint "RESC1005X40X25NL05T10")
      (fields (field (name "MANUFACTURER") "Yageo / Phycomp"))
      (libsource (lib "Altium Content Vault") (part "RES"))
    )
    (comp (ref "R25")
      (value "RC0402JR-070RL")
      (footprint "RESC1005X40X25NL05T10")
      (fields (field (name "MANUFACTURER") "Yageo / Phycomp"))
      (libsource (lib "Altium Content Vault") (part "RES"))
    )
    (comp (ref "R26")
      (value "ERJ-3EKF5101V")
      (footprint "FP-ERJ3EK-MFG")
      (description "RES SMD 5.1K OHM 1% 1/10W 0603")
      (fields (field (name "TOLERANCE") "1%"))
      (libsource (lib "Altium Content Vault") (part "1029c3af85768c4190bb7ad29bc67b5"))
    )
    (comp (ref "R27")
      (value "ERJ-3EKF5101V")
      (footprint "FP-ERJ3EK-MFG")
      (description "RES SMD 5.1K OHM 1% 1/10W 0603")
      (fields (field (name "TOLERANCE") "1%"))
      (libsource (lib "Altium Content Vault") (part "1029c3af85768c4190bb7ad29bc67b5"))
    )
    (comp (ref "R28")
      (value "ERJ-3EKF5101V")
      (footprint "FP-ERJ3EK-MFG")
      (description "RES SMD 5.1K OHM 1% 1/10W 0603")
      (fields (field (name "TOLERANCE") "1%"))
      (libsource (lib "Altium Content Vault") (part "1029c3af85768c4190bb7ad29bc67b5"))
    )
    (comp (ref "R29")
      (value "ERJ-3EKF5101V")
      (footprint "FP-ERJ3EK-MFG")
      (description "RES SMD 5.1K OHM 1% 1/10W 0603")
      (fields (field (name "TOLERANCE") "1%"))
      (libsource (lib "Altium Content Vault") (part "1029c3af85768c4190bb7ad29bc67b5"))
    )
    (comp (ref "TP1")
      (value "TPAD6R")
      (footprint "New footprint 1")
      (description "Test Point .6mm")
      (libsource (lib "Space Concordia") (part "TP"))
    )
    (comp (ref "TP2")
      (value "TPAD6R")
      (footprint "New footprint 1")
      (description "Test Point .6mm")
      (libsource (lib "Space Concordia") (part "TP"))
    )
    (comp (ref "TP3")
      (value "TPAD6R")
      (footprint "New footprint 1")
      (description "Test Point .6mm")
      (libsource (lib "Space Concordia") (part "TP"))
    )
    (comp (ref "TP4")
      (value "TPAD6R")
      (footprint "New footprint 1")
      (description "Test Point .6mm")
      (libsource (lib "Space Concordia") (part "TP"))
    )
    (comp (ref "TP40")
      (value "TPAD6R")
      (footprint "New footprint 1")
      (description "Test Point .6mm")
      (libsource (lib "Space Concordia") (part "TP"))
    )
    (comp (ref "TP41")
      (value "TPAD6R")
      (footprint "New footprint 1")
      (description "Test Point .6mm")
      (libsource (lib "Space Concordia") (part "TP"))
    )
    (comp (ref "TP42")
      (value "TPAD6R")
      (footprint "New footprint 1")
      (description "Test Point .6mm")
      (libsource (lib "Space Concordia") (part "TP"))
    )
    (comp (ref "TP43")
      (value "TPAD6R")
      (footprint "New footprint 1")
      (description "Test Point .6mm")
      (libsource (lib "Space Concordia") (part "TP"))
    )
    (comp (ref "TP44")
      (value "TPAD6R")
      (footprint "New footprint 1")
      (description "Test Point .6mm")
      (libsource (lib "Space Concordia") (part "TP"))
    )
    (comp (ref "TP45")
      (value "TPAD6R")
      (footprint "New footprint 1")
      (description "Test Point .6mm")
      (libsource (lib "Space Concordia") (part "TP"))
    )
    (comp (ref "TP46")
      (value "TPAD6R")
      (footprint "New footprint 1")
      (description "Test Point .6mm")
      (libsource (lib "Space Concordia") (part "TP"))
    )
    (comp (ref "TP47")
      (value "TPAD6R")
      (footprint "New footprint 1")
      (description "Test Point .6mm")
      (libsource (lib "Space Concordia") (part "TP"))
    )
    (comp (ref "TP48")
      (value "TPAD6R")
      (footprint "New footprint 1")
      (description "Test Point .6mm")
      (libsource (lib "Space Concordia") (part "TP"))
    )
    (comp (ref "TP49")
      (value "TPAD6R")
      (footprint "New footprint 1")
      (description "Test Point .6mm")
      (libsource (lib "Space Concordia") (part "TP"))
    )
    (comp (ref "TP50")
      (value "TPAD6R")
      (footprint "New footprint 1")
      (description "Test Point .6mm")
      (libsource (lib "Space Concordia") (part "TP"))
    )
    (comp (ref "TP51")
      (value "TPAD6R")
      (footprint "New footprint 1")
      (description "Test Point .6mm")
      (libsource (lib "Space Concordia") (part "TP"))
    )
    (comp (ref "TP52")
      (value "TPAD6R")
      (footprint "New footprint 1")
      (description "Test Point .6mm")
      (libsource (lib "Space Concordia") (part "TP"))
    )
    (comp (ref "TP53")
      (value "TPAD6R")
      (footprint "New footprint 1")
      (description "Test Point .6mm")
      (libsource (lib "Space Concordia") (part "TP"))
    )
    (comp (ref "U1")
      (value "MAX96724FGTN/V+")
      (footprint "MAX96724FGTN_V+-Footprint-1")
      (description "Quad Tunneling GMSL2/1 to CSI-2 Deserializer")
      (libsource (lib "Space Concordia") (part "MAX96724FGTN_V+-Symbol-1"))
    )
    (comp (ref "U2")
      (value "LD1117S18TR")
      (footprint "SOT-223_M")
      (description "Fixed Low Drop Positive Voltage Regulator, 1.8V, 4-Pin SOT-223, Tape and Reel")
      (libsource (lib "Altium Content Vault") (part "PM-REG-LD1117-SOT4"))
    )
    (comp (ref "U3")
      (value "LD1117S12TR")
      (footprint "SOT-223_M")
      (description "Fixed Low Drop Positive Voltage Regulator, 1.2V, 4-Pin SOT-223, Tape and Reel")
      (libsource (lib "Altium Content Vault") (part "PM-REG-LD1117-SOT4"))
    )
    (comp (ref "Y1")
      (value "ABM8G-25.000MHZ-18-D2Y-T")
      (footprint "FP-ABM8G-MFG")
      (description "Crystal 25MHz ±20ppm (Tol) ±30ppm (Stability) 18pF FUND 60Ω 4-Pin SMD T/R")
      (fields (field (name "TOLERANCE") "20ppm"))
      (libsource (lib "Altium Content Vault") (part "48e526d86b7f2615d98721063c72f49"))
    )
  )
  (nets
    (net (code "1") (name "/CAM_1V2") (class "Default")
      (node (ref "C51") (pin "1") (pinfunction "1_1") (pintype "passive"))
      (node (ref "R20") (pin "1") (pinfunction "1_1") (pintype "passive"))
      (node (ref "R21") (pin "1") (pinfunction "1_1") (pintype "passive"))
      (node (ref "R25") (pin "1") (pinfunction "1_1") (pintype "passive"))
      (node (ref "U3") (pin "2") (pinfunction "VOUT_2") (pintype "power_in"))
      (node (ref "U3") (pin "4") (pinfunction "VOUT_4") (pintype "power_in"))
    )
    (net (code "2") (name "/CAM_1V8") (class "Default")
      (node (ref "C50") (pin "1") (pinfunction "1_1") (pintype "passive"))
      (node (ref "R22") (pin "1") (pinfunction "1_1") (pintype "passive"))
      (node (ref "R23") (pin "1") (pinfunction "1_1") (pintype "passive"))
      (node (ref "U2") (pin "2") (pinfunction "VOUT_2") (pintype "power_in"))
      (node (ref "U2") (pin "4") (pinfunction "VOUT_4") (pintype "power_in"))
    )
    (net (code "3") (name "/CAM_I2C_SCL") (class "Default")
      (node (ref "R19") (pin "1") (pinfunction "1_1") (pintype "passive"))
      (node (ref "TP42") (pin "1") (pinfunction "TP_1") (pintype "passive"))
      (node (ref "U1") (pin "29") (pinfunction "SCL_29") (pintype "passive"))
    )
    (net (code "4") (name "/CAM_I2C_SDA") (class "Default")
      (node (ref "R15") (pin "1") (pinfunction "1_1") (pintype "passive"))
      (node (ref "TP40") (pin "1") (pinfunction "TP_1") (pintype "passive"))
      (node (ref "U1") (pin "28") (pinfunction "SDA_28") (pintype "passive"))
    )
    (net (code "5") (name "/CFG0") (class "Default")
      (node (ref "R11") (pin "1") (pinfunction "1_1") (pintype "passive"))
      (node (ref "R14") (pin "2") (pinfunction "2_2") (pintype "passive"))
      (node (ref "TP53") (pin "1") (pinfunction "TP_1") (pintype "passive"))
      (node (ref "U1") (pin "4") (pinfunction "CFG0_4") (pintype "input"))
    )
    (net (code "6") (name "/CKA_N") (class "Default")
      (node (ref "TP2") (pin "1") (pinfunction "TP_1") (pintype "passive"))
      (node (ref "U1") (pin "40") (pinfunction "CKAN_40") (pintype "bidirectional"))
    )
    (net (code "7") (name "/CKA_P") (class "Default")
      (node (ref "TP1") (pin "1") (pinfunction "TP_1") (pintype "passive"))
      (node (ref "U1") (pin "39") (pinfunction "CKAP_39") (pintype "bidirectional"))
    )
    (net (code "8") (name "/CKB_N") (class "Default")
      (node (ref "C28") (pin "2") (pinfunction "2_2") (pintype "passive"))
      (node (ref "U1") (pin "46") (pinfunction "NC/CKBN_46") (pintype "passive"))
    )
    (net (code "9") (name "/CKB_P") (class "Default")
      (node (ref "C25") (pin "2") (pinfunction "2_2") (pintype "passive"))
      (node (ref "U1") (pin "45") (pinfunction "NC/CKBP_45") (pintype "passive"))
    )
    (net (code "10") (name "/CKC_N") (class "Default")
      (node (ref "C14") (pin "2") (pinfunction "2_2") (pintype "passive"))
      (node (ref "U1") (pin "34") (pinfunction "CKCN_34") (pintype "bidirectional"))
    )
    (net (code "11") (name "/CKC_P") (class "Default")
      (node (ref "C11") (pin "2") (pinfunction "2_2") (pintype "passive"))
      (node (ref "U1") (pin "33") (pinfunction "CKCP_33") (pintype "bidirectional"))
    )
    (net (code "12") (name "/CKF_N") (class "Default")
      (node (ref "TP4") (pin "1") (pinfunction "TP_1") (pintype "passive"))
      (node (ref "U1") (pin "52") (pinfunction "NC/CKFN_52") (pintype "passive"))
    )
    (net (code "13") (name "/CKF_P") (class "Default")
      (node (ref "TP3") (pin "1") (pinfunction "TP_1") (pintype "passive"))
      (node (ref "U1") (pin "51") (pinfunction "NC/CKFP_51") (pintype "passive"))
    )
    (net (code "14") (name "/CSI0_CK_N") (class "Default")
      (node (ref "C14") (pin "1") (pinfunction "1_1") (pintype "passive"))
    )
    (net (code "15") (name "/CSI0_CK_P") (class "Default")
      (node (ref "C11") (pin "1") (pinfunction "1_1") (pintype "passive"))
    )
    (net (code "16") (name "/CSI0_D0_N") (class "Default")
      (node (ref "C2") (pin "1") (pinfunction "1_1") (pintype "passive"))
    )
    (net (code "17") (name "/CSI0_D0_P") (class "Default")
      (node (ref "C1") (pin "1") (pinfunction "1_1") (pintype "passive"))
    )
    (net (code "18") (name "/CSI0_D1_N") (class "Default")
      (node (ref "C4") (pin "1") (pinfunction "1_1") (pintype "passive"))
    )
    (net (code "19") (name "/CSI0_D1_P") (class "Default")
      (node (ref "C3") (pin "1") (pinfunction "1_1") (pintype "passive"))
    )
    (net (code "20") (name "/CSI0_D2_N") (class "Default")
      (node (ref "C6") (pin "1") (pinfunction "1_1") (pintype "passive"))
    )
    (net (code "21") (name "/CSI0_D2_P") (class "Default")
      (node (ref "C5") (pin "1") (pinfunction "1_1") (pintype "passive"))
    )
    (net (code "22") (name "/CSI0_D3_N") (class "Default")
      (node (ref "C10") (pin "1") (pinfunction "1_1") (pintype "passive"))
    )
    (net (code "23") (name "/CSI0_D3_P") (class "Default")
      (node (ref "C9") (pin "1") (pinfunction "1_1") (pintype "passive"))
    )
    (net (code "24") (name "/CSI1_CK_N") (class "Default")
      (node (ref "C28") (pin "1") (pinfunction "1_1") (pintype "passive"))
    )
    (net (code "25") (name "/CSI1_CK_P") (class "Default")
      (node (ref "C25") (pin "1") (pinfunction "1_1") (pintype "passive"))
    )
    (net (code "26") (name "/CSI1_D0_N") (class "Default")
      (node (ref "C16") (pin "1") (pinfunction "1_1") (pintype "passive"))
    )
    (net (code "27") (name "/CSI1_D0_P") (class "Default")
      (node (ref "C15") (pin "1") (pinfunction "1_1") (pintype "passive"))
    )
    (net (code "28") (name "/CSI1_D1_N") (class "Default")
      (node (ref "C18") (pin "1") (pinfunction "1_1") (pintype "passive"))
    )
    (net (code "29") (name "/CSI1_D1_P") (class "Default")
      (node (ref "C17") (pin "1") (pinfunction "1_1") (pintype "passive"))
    )
    (net (code "30") (name "/CSI1_D2_N") (class "Default")
      (node (ref "C20") (pin "1") (pinfunction "1_1") (pintype "passive"))
    )
    (net (code "31") (name "/CSI1_D2_P") (class "Default")
      (node (ref "C19") (pin "1") (pinfunction "1_1") (pintype "passive"))
    )
    (net (code "32") (name "/CSI1_D3_N") (class "Default")
      (node (ref "C24") (pin "1") (pinfunction "1_1") (pintype "passive"))
    )
    (net (code "33") (name "/CSI1_D3_P") (class "Default")
      (node (ref "C23") (pin "1") (pinfunction "1_1") (pintype "passive"))
    )
    (net (code "34") (name "/DA0_N") (class "Default")
      (node (ref "C2") (pin "2") (pinfunction "2_2") (pintype "passive"))
      (node (ref "U1") (pin "32") (pinfunction "DA0N_32") (pintype "bidirectional"))
    )
    (net (code "35") (name "/DA0_P") (class "Default")
      (node (ref "C1") (pin "2") (pinfunction "2_2") (pintype "passive"))
      (node (ref "U1") (pin "31") (pinfunction "DA0P_31") (pintype "bidirectional"))
    )
    (net (code "36") (name "/DA1_N") (class "Default")
      (node (ref "C4") (pin "2") (pinfunction "2_2") (pintype "passive"))
      (node (ref "U1") (pin "36") (pinfunction "DA1N_36") (pintype "bidirectional"))
    )
    (net (code "37") (name "/DA1_P") (class "Default")
      (node (ref "C3") (pin "2") (pinfunction "2_2") (pintype "passive"))
      (node (ref "U1") (pin "35") (pinfunction "DA1P_35") (pintype "bidirectional"))
    )
    (net (code "38") (name "/DA2_N") (class "Default")
      (node (ref "C6") (pin "2") (pinfunction "2_2") (pintype "passive"))
      (node (ref "U1") (pin "38") (pinfunction "DA2N_38") (pintype "bidirectional"))
    )
    (net (code "39") (name "/DA2_P") (class "Default")
      (node (ref "C5") (pin "2") (pinfunction "2_2") (pintype "passive"))
      (node (ref "U1") (pin "37") (pinfunction "DA2P_37") (pintype "bidirectional"))
    )
    (net (code "40") (name "/DA3_N") (class "Default")
      (node (ref "C10") (pin "2") (pinfunction "2_2") (pintype "passive"))
      (node (ref "U1") (pin "42") (pinfunction "DA3N_42") (pintype "bidirectional"))
    )
    (net (code "41") (name "/DA3_P") (class "Default")
      (node (ref "C9") (pin "2") (pinfunction "2_2") (pintype "passive"))
      (node (ref "U1") (pin "41") (pinfunction "DA3P_41") (pintype "bidirectional"))
    )
    (net (code "42") (name "/DB0_N") (class "Default")
      (node (ref "C16") (pin "2") (pinfunction "2_2") (pintype "passive"))
      (node (ref "U1") (pin "44") (pinfunction "NC/DB0N_44") (pintype "passive"))
    )
    (net (code "43") (name "/DB0_P") (class "Default")
      (node (ref "C15") (pin "2") (pinfunction "2_2") (pintype "passive"))
      (node (ref "U1") (pin "43") (pinfunction "NC/DB0P_43") (pintype "passive"))
    )
    (net (code "44") (name "/DB1_N") (class "Default")
      (node (ref "C18") (pin "2") (pinfunction "2_2") (pintype "passive"))
      (node (ref "U1") (pin "48") (pinfunction "NC/DB1N_48") (pintype "passive"))
    )
    (net (code "45") (name "/DB1_P") (class "Default")
      (node (ref "C17") (pin "2") (pinfunction "2_2") (pintype "passive"))
      (node (ref "U1") (pin "47") (pinfunction "NC/DB1P_47") (pintype "passive"))
    )
    (net (code "46") (name "/DB2_N") (class "Default")
      (node (ref "C20") (pin "2") (pinfunction "2_2") (pintype "passive"))
      (node (ref "U1") (pin "50") (pinfunction "NC/DB2N_50") (pintype "passive"))
    )
    (net (code "47") (name "/DB2_P") (class "Default")
      (node (ref "C19") (pin "2") (pinfunction "2_2") (pintype "passive"))
      (node (ref "U1") (pin "49") (pinfunction "NC/DB2P_49") (pintype "passive"))
    )
    (net (code "48") (name "/DB3_N") (class "Default")
      (node (ref "C24") (pin "2") (pinfunction "2_2") (pintype "passive"))
      (node (ref "U1") (pin "54") (pinfunction "NC/DB3N_54") (pintype "passive"))
    )
    (net (code "49") (name "/DB3_P") (class "Default")
      (node (ref "C23") (pin "2") (pinfunction "2_2") (pintype "passive"))
      (node (ref "U1") (pin "53") (pinfunction "NC/DB3P_53") (pintype "passive"))
    )
    (net (code "50") (name "/MFP0") (class "Default")
      (node (ref "TP44") (pin "1") (pinfunction "TP_1") (pintype "passive"))
      (node (ref "U1") (pin "1") (pinfunction "MFP0_1") (pintype "bidirectional"))
    )
    (net (code "51") (name "/MFP1") (class "Default")
      (node (ref "TP46") (pin "1") (pinfunction "TP_1") (pintype "passive"))
      (node (ref "U1") (pin "2") (pinfunction "MFP1_2") (pintype "bidirectional"))
    )
    (net (code "52") (name "/MFP2") (class "Default")
      (node (ref "TP48") (pin "1") (pinfunction "TP_1") (pintype "passive"))
      (node (ref "U1") (pin "3") (pinfunction "MFP2_3") (pintype "bidirectional"))
    )
    (net (code "53") (name "/MFP3") (class "Default")
      (node (ref "TP41") (pin "1") (pinfunction "TP_1") (pintype "passive"))
      (node (ref "U1") (pin "12") (pinfunction "MFP3_12") (pintype "bidirectional"))
    )
    (net (code "54") (name "/MFP4") (class "Default")
      (node (ref "TP43") (pin "1") (pinfunction "TP_1") (pintype "passive"))
      (node (ref "U1") (pin "13") (pinfunction "MFP4_13") (pintype "bidirectional"))
    )
    (net (code "55") (name "/MFP5") (class "Default")
      (node (ref "TP45") (pin "1") (pinfunction "TP_1") (pintype "passive"))
      (node (ref "U1") (pin "14") (pinfunction "MFP5_14") (pintype "bidirectional"))
    )
    (net (code "56") (name "/MFP6") (class "Default")
      (node (ref "R10") (pin "1") (pinfunction "1_1") (pintype "passive"))
      (node (ref "R13") (pin "2") (pinfunction "2_2") (pintype "passive"))
      (node (ref "TP47") (pin "1") (pinfunction "TP_1") (pintype "passive"))
      (node (ref "U1") (pin "25") (pinfunction "CFG1/MFP6_25") (pintype "bidirectional"))
    )
    (net (code "57") (name "/MFP7") (class "Default")
      (node (ref "TP49") (pin "1") (pinfunction "TP_1") (pintype "passive"))
      (node (ref "U1") (pin "26") (pinfunction "SDA1/MFP7_26") (pintype "bidirectional"))
    )
    (net (code "58") (name "/MFP8") (class "Default")
      (node (ref "TP50") (pin "1") (pinfunction "TP_1") (pintype "passive"))
      (node (ref "U1") (pin "27") (pinfunction "SCL1/MFP8_27") (pintype "bidirectional"))
    )
    (net (code "59") (name "/PoC_A") (class "Default")
      (node (ref "C7") (pin "2") (pinfunction "2_2") (pintype "passive"))
      (node (ref "D22") (pin "1") (pinfunction "IO1_1") (pintype "bidirectional"))
      (node (ref "D22") (pin "10") (pinfunction "NC_10") (pintype "passive"))
      (node (ref "J2") (pin "3") (pinfunction "3_3") (pintype "passive"))
      (node (ref "L2") (pin "2") (pinfunction "2_2") (pintype "passive"))
    )
    (net (code "60") (name "/PoC_B") (class "Default")
      (node (ref "C8") (pin "2") (pinfunction "2_2") (pintype "passive"))
      (node (ref "D23") (pin "5") (pinfunction "IO4_5") (pintype "bidirectional"))
      (node (ref "D23") (pin "6") (pinfunction "NC_6") (pintype "passive"))
      (node (ref "J2") (pin "4") (pinfunction "4_4") (pintype "passive"))
      (node (ref "L4") (pin "2") (pinfunction "2_2") (pintype "passive"))
    )
    (net (code "61") (name "/PoC_C") (class "Default")
      (node (ref "C21") (pin "2") (pinfunction "2_2") (pintype "passive"))
      (node (ref "D24") (pin "1") (pinfunction "IO1_1") (pintype "bidirectional"))
      (node (ref "D24") (pin "10") (pinfunction "NC_10") (pintype "passive"))
      (node (ref "J2") (pin "1") (pinfunction "1_1") (pintype "passive"))
      (node (ref "L6") (pin "2") (pinfunction "2_2") (pintype "passive"))
    )
    (net (code "62") (name "/PoC_D") (class "Default")
      (node (ref "C22") (pin "2") (pinfunction "2_2") (pintype "passive"))
      (node (ref "D25") (pin "5") (pinfunction "IO4_5") (pintype "bidirectional"))
      (node (ref "D25") (pin "6") (pinfunction "NC_6") (pintype "passive"))
      (node (ref "J2") (pin "2") (pinfunction "2_2") (pintype "passive"))
      (node (ref "L8") (pin "2") (pinfunction "2_2") (pintype "passive"))
    )
    (net (code "63") (name "/PoC_PWR") (class "Default")
      (node (ref "F2") (pin "1") (pinfunction "1_1") (pintype "passive"))
      (node (ref "F3") (pin "1") (pinfunction "1_1") (pintype "passive"))
      (node (ref "F4") (pin "1") (pinfunction "1_1") (pintype "passive"))
      (node (ref "F5") (pin "1") (pinfunction "1_1") (pintype "passive"))
      (node (ref "TP52") (pin "1") (pinfunction "TP_1") (pintype "passive"))
    )
    (net (code "64") (name "/SIOA_N") (class "Default")
      (node (ref "C12") (pin "1") (pinfunction "1_1") (pintype "passive"))
      (node (ref "U1") (pin "22") (pinfunction "SIOAN_22") (pintype "bidirectional"))
    )
    (net (code "65") (name "/SIOA_P") (class "Default")
      (node (ref "C7") (pin "1") (pinfunction "1_1") (pintype "passive"))
      (node (ref "U1") (pin "23") (pinfunction "SIOAP_23") (pintype "bidirectional"))
    )
    (net (code "66") (name "/SIOB_N") (class "Default")
      (node (ref "C13") (pin "1") (pinfunction "1_1") (pintype "passive"))
      (node (ref "U1") (pin "19") (pinfunction "SIOBN_19") (pintype "bidirectional"))
    )
    (net (code "67") (name "/SIOB_P") (class "Default")
      (node (ref "C8") (pin "1") (pinfunction "1_1") (pintype "passive"))
      (node (ref "U1") (pin "18") (pinfunction "SIOBP_18") (pintype "bidirectional"))
    )
    (net (code "68") (name "/SIOC_N") (class "Default")
      (node (ref "C26") (pin "1") (pinfunction "1_1") (pintype "passive"))
      (node (ref "U1") (pin "9") (pinfunction "SIOCN_9") (pintype "bidirectional"))
    )
    (net (code "69") (name "/SIOC_P") (class "Default")
      (node (ref "C21") (pin "1") (pinfunction "1_1") (pintype "passive"))
      (node (ref "U1") (pin "10") (pinfunction "SIOCP_10") (pintype "bidirectional"))
    )
    (net (code "70") (name "/SIOD_N") (class "Default")
      (node (ref "C27") (pin "1") (pinfunction "1_1") (pintype "passive"))
      (node (ref "U1") (pin "6") (pinfunction "SIODN_6") (pintype "bidirectional"))
    )
    (net (code "71") (name "/SIOD_P") (class "Default")
      (node (ref "C22") (pin "1") (pinfunction "1_1") (pintype "passive"))
      (node (ref "U1") (pin "5") (pinfunction "SIODP_5") (pintype "bidirectional"))
    )
    (net (code "72") (name "/X25_N") (class "Default")
      (node (ref "C30") (pin "1") (pinfunction "1_1") (pintype "passive"))
      (node (ref "U1") (pin "16") (pinfunction "X2_16") (pintype "passive"))
      (node (ref "Y1") (pin "3") (pinfunction "3_3") (pintype "passive"))
    )
    (net (code "73") (name "/X25_P") (class "Default")
      (node (ref "C29") (pin "1") (pinfunction "1_1") (pintype "passive"))
      (node (ref "U1") (pin "15") (pinfunction "X1/OSC_15") (pintype "passive"))
      (node (ref "Y1") (pin "1") (pinfunction "1_1") (pintype "passive"))
    )
    (net (code "74") (name "/XRES") (class "Default")
      (node (ref "R18") (pin "2") (pinfunction "2_2") (pintype "passive"))
      (node (ref "U1") (pin "17") (pinfunction "XRES_17") (pintype "passive"))
    )
    (net (code "75") (name "/nPWDN") (class "Default")
      (node (ref "R12") (pin "2") (pinfunction "2_2") (pintype "passive"))
      (node (ref "TP51") (pin "1") (pinfunction "TP_1") (pintype "passive"))
    )
    (net (code "76") (name "2V_AUX") (class "Default")
      (node (ref "C52") (pin "2") (pinfunction "2_2") (pintype "passive"))
      (node (ref "C53") (pin "2") (pinfunction "2_2") (pintype "passive"))
      (node (ref "U2") (pin "3") (pinfunction "VIN_3") (pintype "power_in"))
      (node (ref "U3") (pin "3") (pinfunction "VIN_3") (pintype "power_in"))
    )
    (net (code "77") (name "3V3_AUX") (class "Default")
      (node (ref "R10") (pin "2") (pinfunction "2_2") (pintype "passive"))
      (node (ref "R11") (pin "2") (pinfunction "2_2") (pintype "passive"))
      (node (ref "R15") (pin "2") (pinfunction "2_2") (pintype "passive"))
      (node (ref "R19") (pin "2") (pinfunction "2_2") (pintype "passive"))
      (node (ref "R24") (pin "1") (pinfunction "1_1") (pintype "passive"))
      (node (ref "R7") (pin "2") (pinfunction "2_2") (pintype "passive"))
    )
    (net (code "78") (name "GND") (class "Default")
      (node (ref "C29") (pin "2") (pinfunction "2_2") (pintype "passive"))
      (node (ref "C30") (pin "2") (pinfunction "2_2") (pintype "passive"))
      (node (ref "C31") (pin "2") (pinfunction "2_2") (pintype "passive"))
      (node (ref "C32") (pin "1") (pinfunction "1_1") (pintype "passive"))
      (node (ref "C33") (pin "2") (pinfunction "2_2") (pintype "passive"))
      (node (ref "C34") (pin "1") (pinfunction "1_1") (pintype "passive"))
      (node (ref "C35") (pin "2") (pinfunction "2_2") (pintype "passive"))
      (node (ref "C36") (pin "1") (pinfunction "1_1") (pintype "passive"))
      (node (ref "C37") (pin "2") (pinfunction "2_2") (pintype "passive"))
      (node (ref "C38") (pin "1") (pinfunction "1_1") (pintype "passive"))
      (node (ref "C39") (pin "2") (pinfunction "2_2") (pintype "passive"))
      (node (ref "C40") (pin "1") (pinfunction "1_1") (pintype "passive"))
      (node (ref "C41") (pin "2") (pinfunction "2_2") (pintype "passive"))
      (node (ref "C42") (pin "1") (pinfunction "1_1") (pintype "passive"))
      (node (ref "C43") (pin "2") (pinfunction "2_2") (pintype "passive"))
      (node (ref "C44") (pin "1") (pinfunction "1_1") (pintype "passive"))
      (node (ref "C45") (pin "2") (pinfunction "2_2") (pintype "passive"))
      (node (ref "C46") (pin "1") (pinfunction "1_1") (pintype "passive"))
      (node (ref "C47") (pin "2") (pinfunction "2_2") (pintype "passive"))
      (node (ref "C48") (pin "2") (pinfunction "2_2") (pintype "passive"))
      (node (ref "C49") (pin "2") (pinfunction "2_2") (pintype "passive"))
      (node (ref "C50") (pin "2") (pinfunction "2_2") (pintype "passive"))
      (node (ref "C51") (pin "2") (pinfunction "2_2") (pintype "passive"))
      (node (ref "C52") (pin "1") (pinfunction "1_1") (pintype "passive"))
      (node (ref "C53") (pin "1") (pinfunction "1_1") (pintype "passive"))
      (node (ref "C54") (pin "2") (pinfunction "2_2") (pintype "passive"))
      (node (ref "D22") (pin "3") (pinfunction "GND_3") (pintype "power_in"))
      (node (ref "D22") (pin "8") (pinfunction "GND_8") (pintype "power_in"))
      (node (ref "D23") (pin "3") (pinfunction "GND_3") (pintype "power_in"))
      (node (ref "D23") (pin "8") (pinfunction "GND_8") (pintype "power_in"))
      (node (ref "D24") (pin "3") (pinfunction "GND_3") (pintype "power_in"))
      (node (ref "D24") (pin "8") (pinfunction "GND_8") (pintype "power_in"))
      (node (ref "D25") (pin "3") (pinfunction "GND_3") (pintype "power_in"))
      (node (ref "D25") (pin "8") (pinfunction "GND_8") (pintype "power_in"))
      (node (ref "J2") (pin "MH1") (pinfunction "MH1_MH1") (pintype "passive"))
      (node (ref "J2") (pin "MH2") (pinfunction "MH2_MH2") (pintype "passive"))
      (node (ref "J2") (pin "MH3") (pinfunction "MH3_MH3") (pintype "passive"))
      (node (ref "J2") (pin "MH4") (pinfunction "MH4_MH4") (pintype "passive"))
      (node (ref "J2") (pin "MH5") (pinfunction "MH5_MH5") (pintype "passive"))
      (node (ref "R13") (pin "1") (pinfunction "1_1") (pintype "passive"))
      (node (ref "R14") (pin "1") (pinfunction "1_1") (pintype "passive"))
      (node (ref "R16") (pin "1") (pinfunction "1_1") (pintype "passive"))
      (node (ref "R17") (pin "1") (pinfunction "1_1") (pintype "passive"))
      (node (ref "R18") (pin "1") (pinfunction "1_1") (pintype "passive"))
      (node (ref "R8") (pin "1") (pinfunction "1_1") (pintype "passive"))
      (node (ref "R9") (pin "1") (pinfunction "1_1") (pintype "passive"))
      (node (ref "U1") (pin "57") (pinfunction "GND_(EP)_57") (pintype "power_in"))
      (node (ref "U2") (pin "1") (pinfunction "GND_1") (pintype "power_in"))
      (node (ref "U3") (pin "1") (pinfunction "GND_1") (pintype "power_in"))
      (node (ref "Y1") (pin "2") (pinfunction "GND_2") (pintype "power_in"))
      (node (ref "Y1") (pin "4") (pinfunction "GND_4") (pintype "power_in"))
    )
    (net (code "79") (name "Net-(C12-Pad2)") (class "Default")
      (node (ref "C12") (pin "2") (pinfunction "2_2") (pintype "passive"))
      (node (ref "R8") (pin "2") (pinfunction "2_2") (pintype "passive"))
    )
    (net (code "80") (name "Net-(C13-Pad2)") (class "Default")
      (node (ref "C13") (pin "2") (pinfunction "2_2") (pintype "passive"))
      (node (ref "R9") (pin "2") (pinfunction "2_2") (pintype "passive"))
    )
    (net (code "81") (name "Net-(C26-Pad2)") (class "Default")
      (node (ref "C26") (pin "2") (pinfunction "2_2") (pintype "passive"))
      (node (ref "R16") (pin "2") (pinfunction "2_2") (pintype "passive"))
    )
    (net (code "82") (name "Net-(C27-Pad2)") (class "Default")
      (node (ref "C27") (pin "2") (pinfunction "2_2") (pintype "passive"))
      (node (ref "R17") (pin "2") (pinfunction "2_2") (pintype "passive"))
    )
    (net (code "83") (name "Net-(C31-Pad1)") (class "Default")
      (node (ref "C31") (pin "1") (pinfunction "1_1") (pintype "passive"))
      (node (ref "C32") (pin "2") (pinfunction "2_2") (pintype "passive"))
      (node (ref "U1") (pin "8") (pinfunction "CAP_VDD_8") (pintype "power_in"))
    )
    (net (code "84") (name "Net-(C33-Pad1)") (class "Default")
      (node (ref "C33") (pin "1") (pinfunction "1_1") (pintype "passive"))
      (node (ref "C34") (pin "2") (pinfunction "2_2") (pintype "passive"))
      (node (ref "U1") (pin "20") (pinfunction "CAP_VDD_20") (pintype "power_in"))
    )
    (net (code "85") (name "Net-(C35-Pad1)") (class "Default")
      (node (ref "C35") (pin "1") (pinfunction "1_1") (pintype "passive"))
      (node (ref "C36") (pin "2") (pinfunction "2_2") (pintype "passive"))
      (node (ref "R20") (pin "2") (pinfunction "2_2") (pintype "passive"))
      (node (ref "U1") (pin "55") (pinfunction "VDD_55") (pintype "power_in"))
    )
    (net (code "86") (name "Net-(C37-Pad1)") (class "Default")
      (node (ref "C37") (pin "1") (pinfunction "1_1") (pintype "passive"))
      (node (ref "C38") (pin "2") (pinfunction "2_2") (pintype "passive"))
      (node (ref "R21") (pin "2") (pinfunction "2_2") (pintype "passive"))
      (node (ref "U1") (pin "56") (pinfunction "VDD_56") (pintype "power_in"))
    )
    (net (code "87") (name "Net-(C39-Pad1)") (class "Default")
      (node (ref "C39") (pin "1") (pinfunction "1_1") (pintype "passive"))
      (node (ref "C40") (pin "2") (pinfunction "2_2") (pintype "passive"))
      (node (ref "R22") (pin "2") (pinfunction "2_2") (pintype "passive"))
      (node (ref "U1") (pin "7") (pinfunction "VDD18_7") (pintype "power_in"))
    )
    (net (code "88") (name "Net-(C41-Pad1)") (class "Default")
      (node (ref "C41") (pin "1") (pinfunction "1_1") (pintype "passive"))
      (node (ref "C42") (pin "2") (pinfunction "2_2") (pintype "passive"))
      (node (ref "R23") (pin "2") (pinfunction "2_2") (pintype "passive"))
      (node (ref "U1") (pin "21") (pinfunction "VDD18_21") (pintype "power_in"))
    )
    (net (code "89") (name "Net-(C47-Pad1)") (class "Default")
      (node (ref "C47") (pin "1") (pinfunction "1_1") (pintype "passive"))
      (node (ref "F2") (pin "2") (pinfunction "2_2") (pintype "passive"))
      (node (ref "L1") (pin "1") (pinfunction "1_1") (pintype "passive"))
      (node (ref "R26") (pin "1") (pinfunction "1_1") (pintype "passive"))
    )
    (net (code "90") (name "Net-(C48-Pad1)") (class "Default")
      (node (ref "C48") (pin "1") (pinfunction "1_1") (pintype "passive"))
      (node (ref "F3") (pin "2") (pinfunction "2_2") (pintype "passive"))
      (node (ref "L3") (pin "1") (pinfunction "1_1") (pintype "passive"))
      (node (ref "R27") (pin "1") (pinfunction "1_1") (pintype "passive"))
    )
    (net (code "91") (name "Net-(C49-Pad1)") (class "Default")
      (node (ref "C49") (pin "1") (pinfunction "1_1") (pintype "passive"))
      (node (ref "F4") (pin "2") (pinfunction "2_2") (pintype "passive"))
      (node (ref "L5") (pin "1") (pinfunction "1_1") (pintype "passive"))
      (node (ref "R28") (pin "1") (pinfunction "1_1") (pintype "passive"))
    )
    (net (code "92") (name "Net-(C54-Pad1)") (class "Default")
      (node (ref "C54") (pin "1") (pinfunction "1_1") (pintype "passive"))
      (node (ref "F5") (pin "2") (pinfunction "2_2") (pintype "passive"))
      (node (ref "L7") (pin "1") (pinfunction "1_1") (pintype "passive"))
      (node (ref "R29") (pin "1") (pinfunction "1_1") (pintype "passive"))
    )
    (net (code "93") (name "Net-(L1-Pad2)") (class "Default")
      (node (ref "L1") (pin "2") (pinfunction "2_2") (pintype "passive"))
      (node (ref "L2") (pin "1") (pinfunction "1_1") (pintype "passive"))
      (node (ref "R26") (pin "2") (pinfunction "2_2") (pintype "passive"))
    )
    (net (code "94") (name "Net-(L3-Pad2)") (class "Default")
      (node (ref "L3") (pin "2") (pinfunction "2_2") (pintype "passive"))
      (node (ref "L4") (pin "1") (pinfunction "1_1") (pintype "passive"))
      (node (ref "R27") (pin "2") (pinfunction "2_2") (pintype "passive"))
    )
    (net (code "95") (name "Net-(L5-Pad2)") (class "Default")
      (node (ref "L5") (pin "2") (pinfunction "2_2") (pintype "passive"))
      (node (ref "L6") (pin "1") (pinfunction "1_1") (pintype "passive"))
      (node (ref "R28") (pin "2") (pinfunction "2_2") (pintype "passive"))
    )
    (net (code "96") (name "Net-(L7-Pad2)") (class "Default")
      (node (ref "L7") (pin "2") (pinfunction "2_2") (pintype "passive"))
      (node (ref "L8") (pin "1") (pinfunction "1_1") (pintype "passive"))
      (node (ref "R29") (pin "2") (pinfunction "2_2") (pintype "passive"))
    )
    (net (code "97") (name "Net-(U1A-PWDNB)") (class "Default")
      (node (ref "R12") (pin "1") (pinfunction "1_1") (pintype "passive"))
      (node (ref "R7") (pin "1") (pinfunction "1_1") (pintype "passive"))
      (node (ref "U1") (pin "11") (pinfunction "PWDNB_11") (pintype "input"))
    )
    (net (code "98") (name "Net-(U1B-VDDIO)") (class "Default")
      (node (ref "C43") (pin "1") (pinfunction "1_1") (pintype "passive"))
      (node (ref "C44") (pin "2") (pinfunction "2_2") (pintype "passive"))
      (node (ref "R24") (pin "2") (pinfunction "2_2") (pintype "passive"))
      (node (ref "U1") (pin "24") (pinfunction "VDDIO_24") (pintype "power_in"))
    )
    (net (code "99") (name "Net-(U1B-VTERM)") (class "Default")
      (node (ref "C45") (pin "1") (pinfunction "1_1") (pintype "passive"))
      (node (ref "C46") (pin "2") (pinfunction "2_2") (pintype "passive"))
      (node (ref "R25") (pin "2") (pinfunction "2_2") (pintype "passive"))
      (node (ref "U1") (pin "30") (pinfunction "VTERM_30") (pintype "power_in"))
    )
    (net (code "100") (name "unconnected-(D22-IO2-Pad2)") (class "Default")
      (node (ref "D22") (pin "2") (pinfunction "IO2_2") (pintype "bidirectional"))
    )
    (net (code "101") (name "unconnected-(D22-IO3-Pad4)") (class "Default")
      (node (ref "D22") (pin "4") (pinfunction "IO3_4") (pintype "bidirectional"))
    )
    (net (code "102") (name "unconnected-(D22-IO4-Pad5)") (class "Default")
      (node (ref "D22") (pin "5") (pinfunction "IO4_5") (pintype "bidirectional"))
    )
    (net (code "103") (name "unconnected-(D22-NC-Pad6)") (class "Default")
      (node (ref "D22") (pin "6") (pinfunction "NC_6") (pintype "passive"))
    )
    (net (code "104") (name "unconnected-(D22-NC-Pad7)") (class "Default")
      (node (ref "D22") (pin "7") (pinfunction "NC_7") (pintype "passive"))
    )
    (net (code "105") (name "unconnected-(D22-NC-Pad9)") (class "Default")
      (node (ref "D22") (pin "9") (pinfunction "NC_9") (pintype "passive"))
    )
    (net (code "106") (name "unconnected-(D23-IO1-Pad1)") (class "Default")
      (node (ref "D23") (pin "1") (pinfunction "IO1_1") (pintype "bidirectional"))
    )
    (net (code "107") (name "unconnected-(D23-IO2-Pad2)") (class "Default")
      (node (ref "D23") (pin "2") (pinfunction "IO2_2") (pintype "bidirectional"))
    )
    (net (code "108") (name "unconnected-(D23-IO3-Pad4)") (class "Default")
      (node (ref "D23") (pin "4") (pinfunction "IO3_4") (pintype "bidirectional"))
    )
    (net (code "109") (name "unconnected-(D23-NC-Pad7)") (class "Default")
      (node (ref "D23") (pin "7") (pinfunction "NC_7") (pintype "passive"))
    )
    (net (code "110") (name "unconnected-(D23-NC-Pad9)") (class "Default")
      (node (ref "D23") (pin "9") (pinfunction "NC_9") (pintype "passive"))
    )
    (net (code "111") (name "unconnected-(D23-NC-Pad10)") (class "Default")
      (node (ref "D23") (pin "10") (pinfunction "NC_10") (pintype "passive"))
    )
    (net (code "112") (name "unconnected-(D24-IO2-Pad2)") (class "Default")
      (node (ref "D24") (pin "2") (pinfunction "IO2_2") (pintype "bidirectional"))
    )
    (net (code "113") (name "unconnected-(D24-IO3-Pad4)") (class "Default")
      (node (ref "D24") (pin "4") (pinfunction "IO3_4") (pintype "bidirectional"))
    )
    (net (code "114") (name "unconnected-(D24-IO4-Pad5)") (class "Default")
      (node (ref "D24") (pin "5") (pinfunction "IO4_5") (pintype "bidirectional"))
    )
    (net (code "115") (name "unconnected-(D24-NC-Pad6)") (class "Default")
      (node (ref "D24") (pin "6") (pinfunction "NC_6") (pintype "passive"))
    )
    (net (code "116") (name "unconnected-(D24-NC-Pad7)") (class "Default")
      (node (ref "D24") (pin "7") (pinfunction "NC_7") (pintype "passive"))
    )
    (net (code "117") (name "unconnected-(D24-NC-Pad9)") (class "Default")
      (node (ref "D24") (pin "9") (pinfunction "NC_9") (pintype "passive"))
    )
    (net (code "118") (name "unconnected-(D25-IO1-Pad1)") (class "Default")
      (node (ref "D25") (pin "1") (pinfunction "IO1_1") (pintype "bidirectional"))
    )
    (net (code "119") (name "unconnected-(D25-IO2-Pad2)") (class "Default")
      (node (ref "D25") (pin "2") (pinfunction "IO2_2") (pintype "bidirectional"))
    )
    (net (code "120") (name "unconnected-(D25-IO3-Pad4)") (class "Default")
      (node (ref "D25") (pin "4") (pinfunction "IO3_4") (pintype "bidirectional"))
    )
    (net (code "121") (name "unconnected-(D25-NC-Pad7)") (class "Default")
      (node (ref "D25") (pin "7") (pinfunction "NC_7") (pintype "passive"))
    )
    (net (code "122") (name "unconnected-(D25-NC-Pad9)") (class "Default")
      (node (ref "D25") (pin "9") (pinfunction "NC_9") (pintype "passive"))
    )
    (net (code "123") (name "unconnected-(D25-NC-Pad10)") (class "Default")
      (node (ref "D25") (pin "10") (pinfunction "NC_10") (pintype "passive"))
    )
  )
)
